# 3.net
KiCad netlist of a schematic drawn in EasyEDA Pro
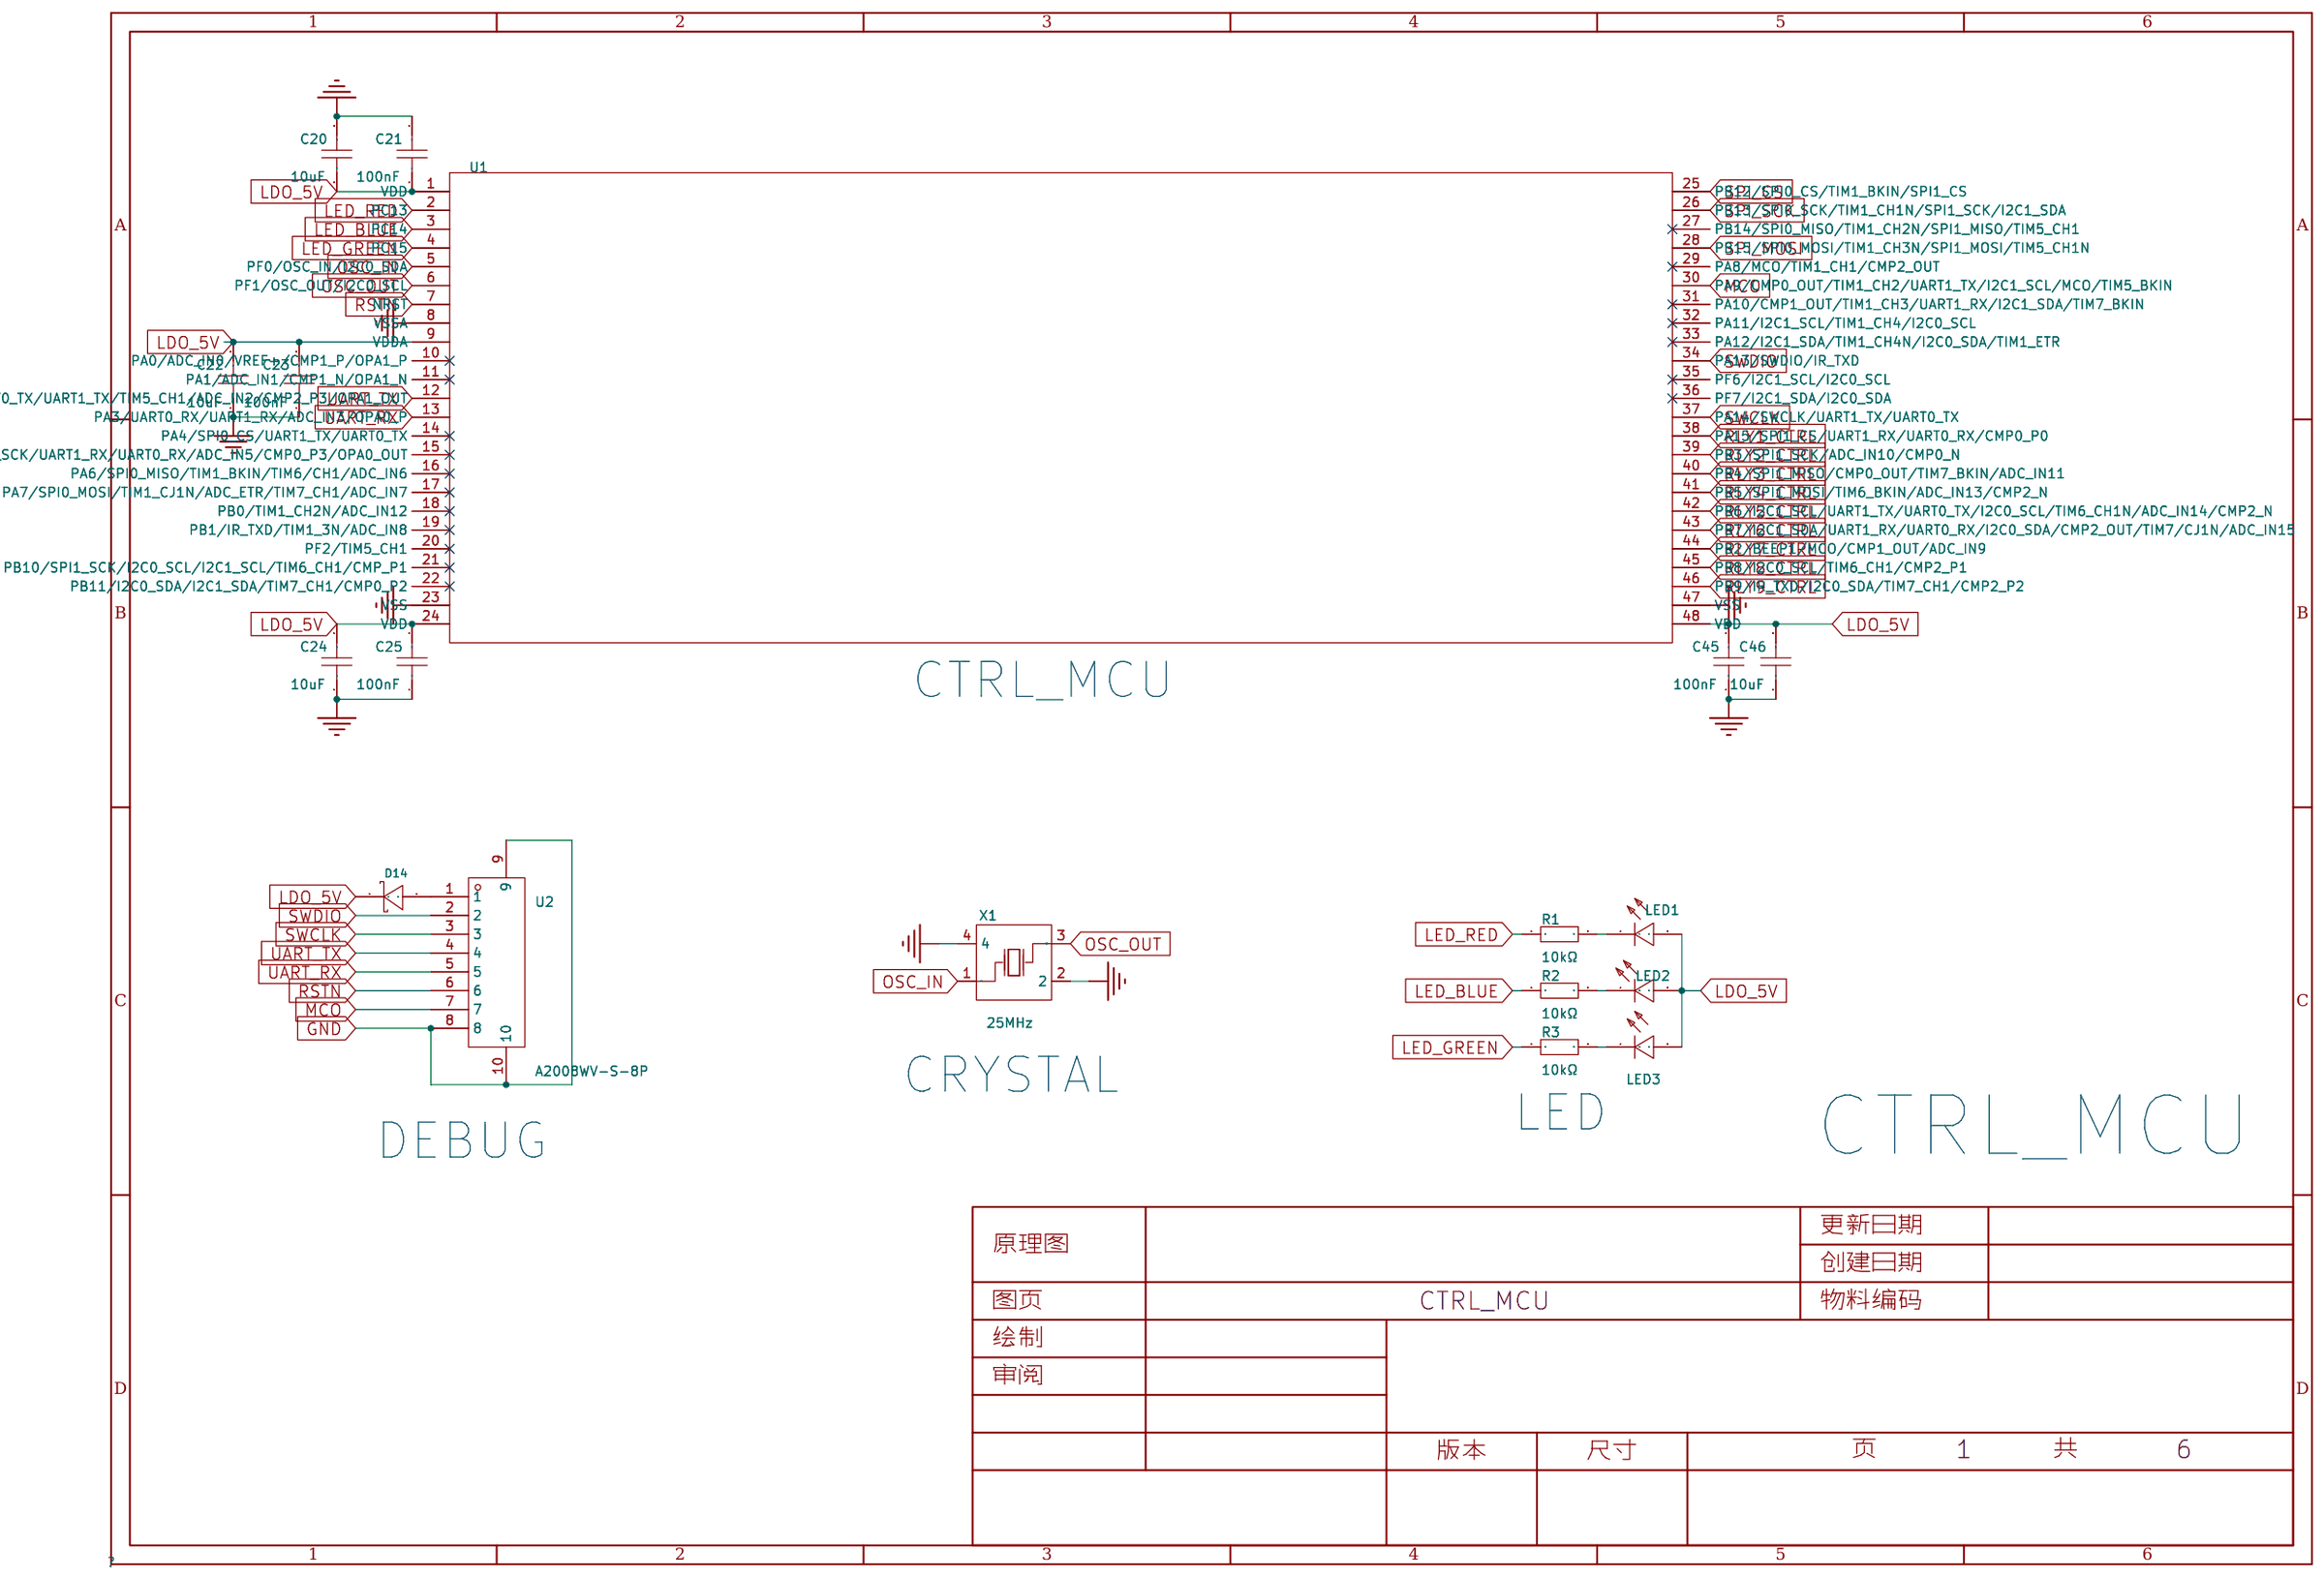
[diagram p0: CTRL_MCU]
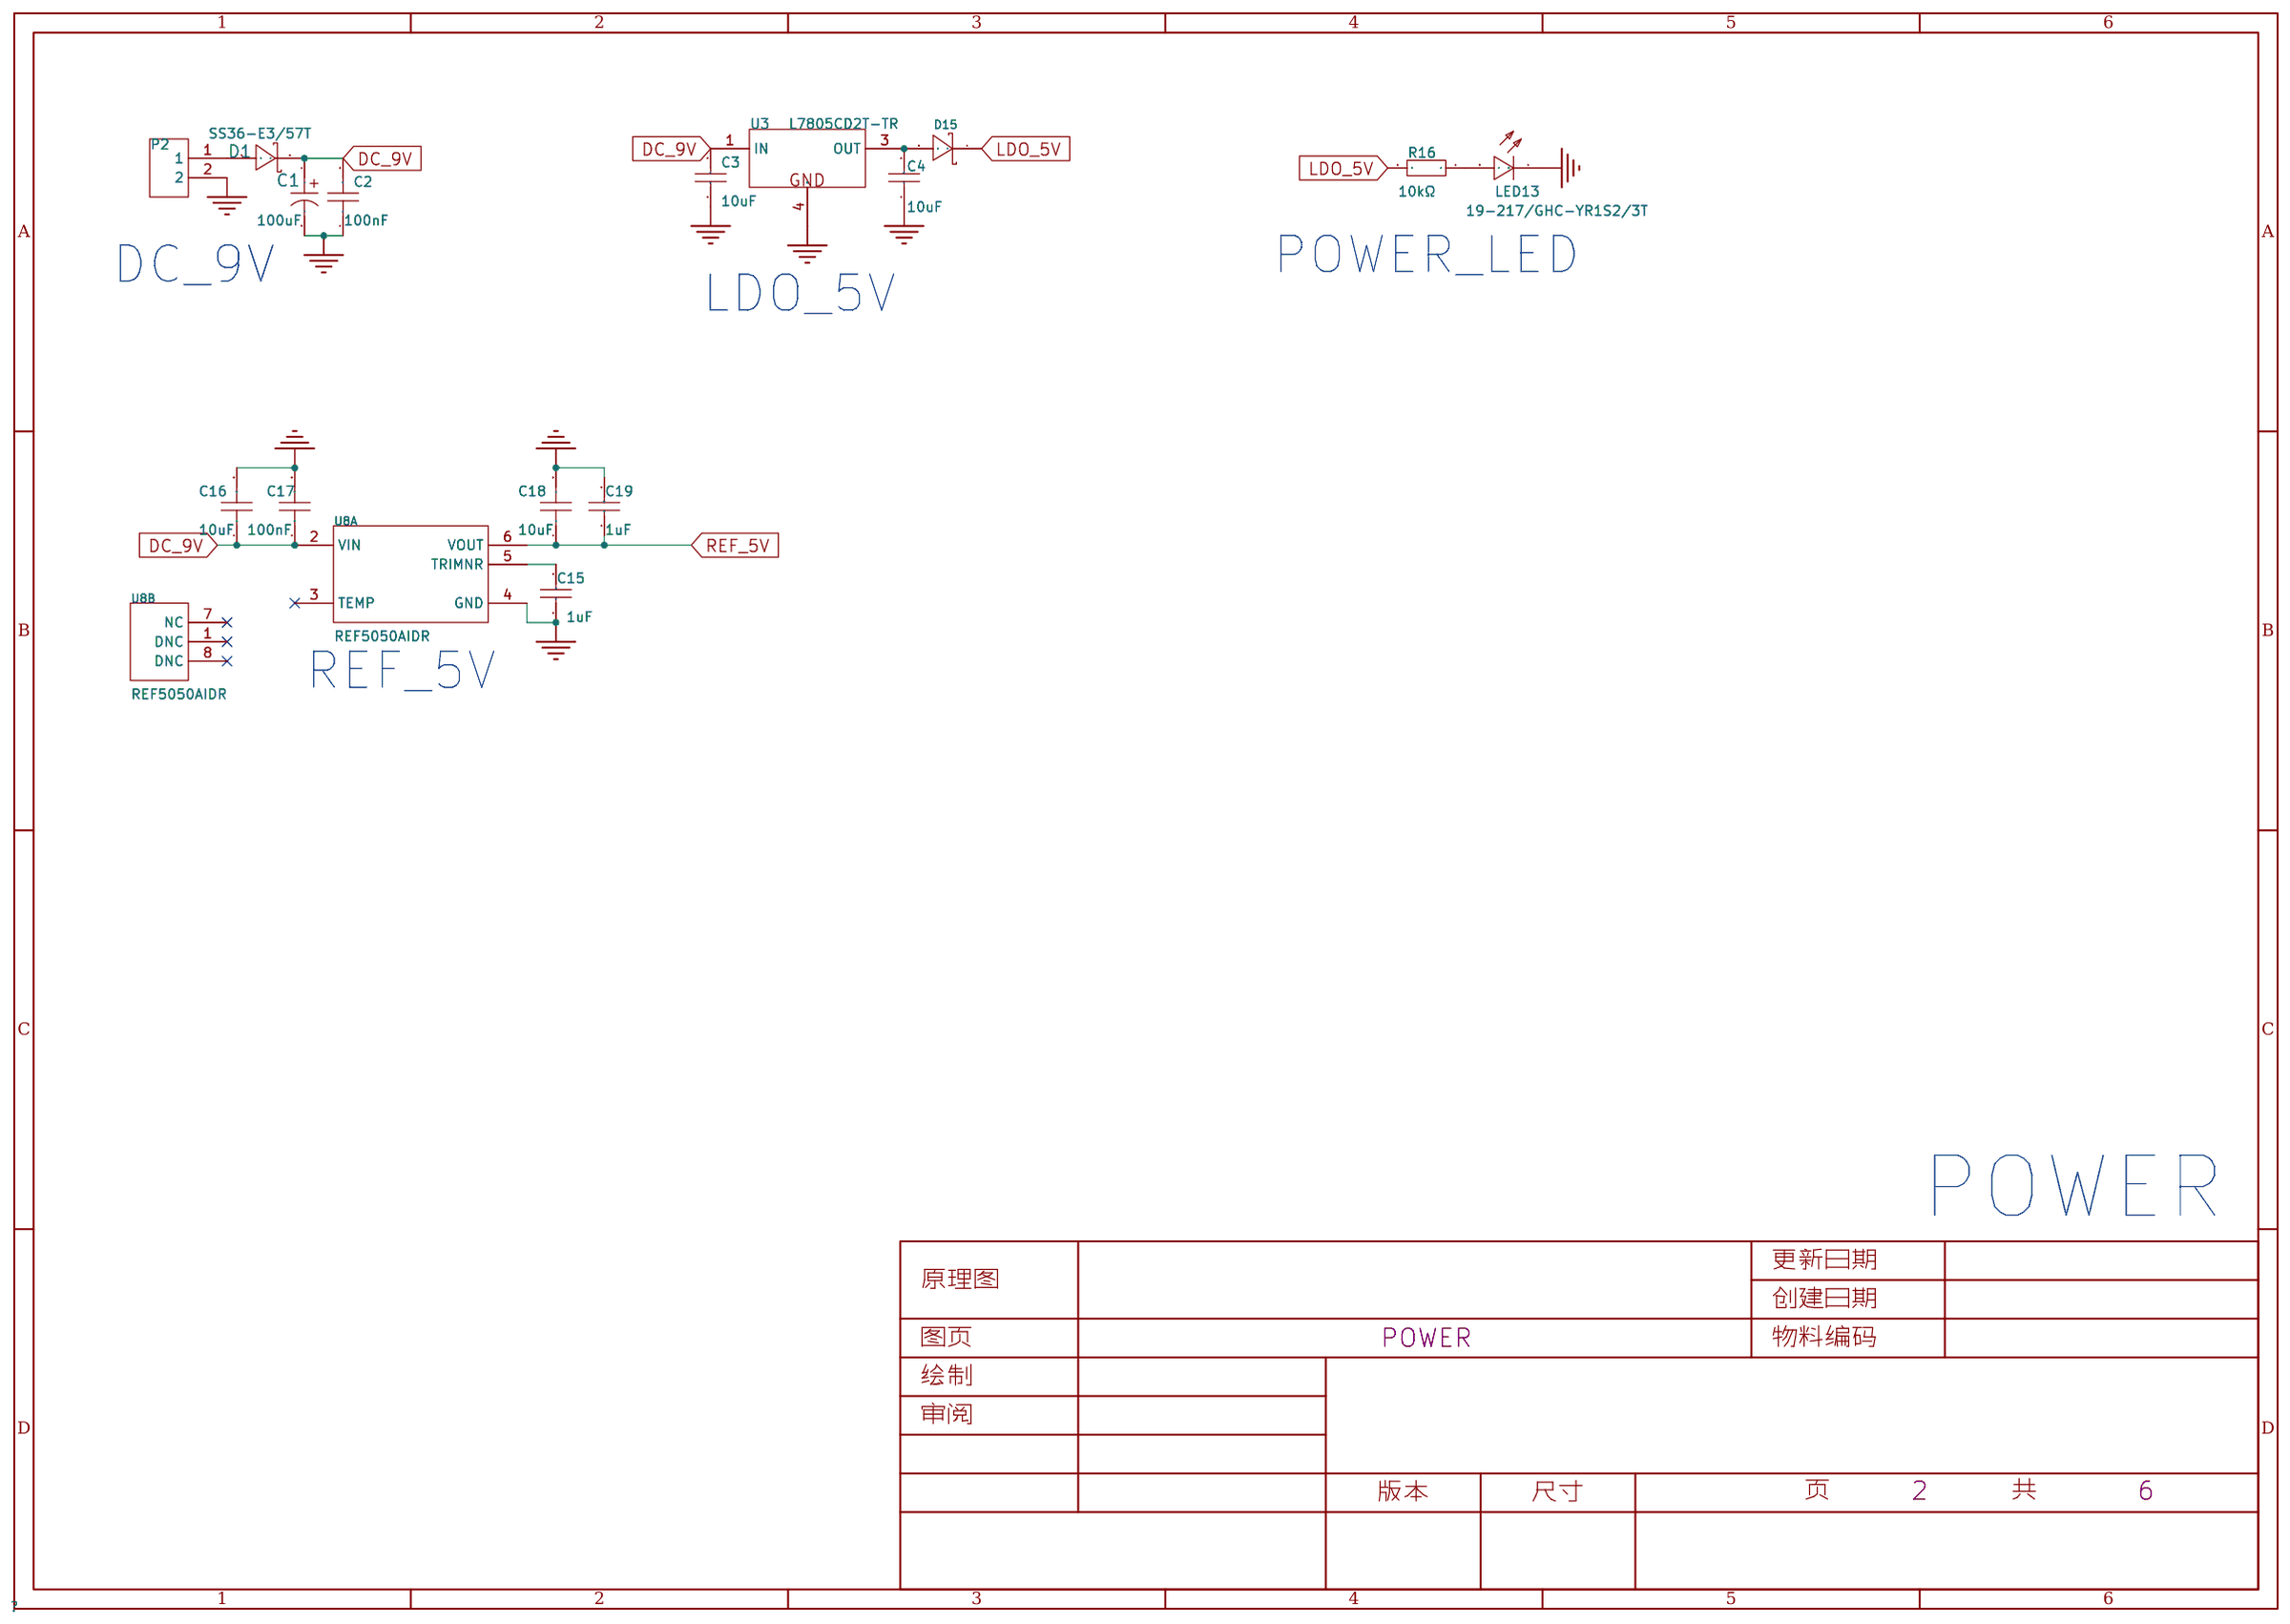
[diagram p1: POWER]
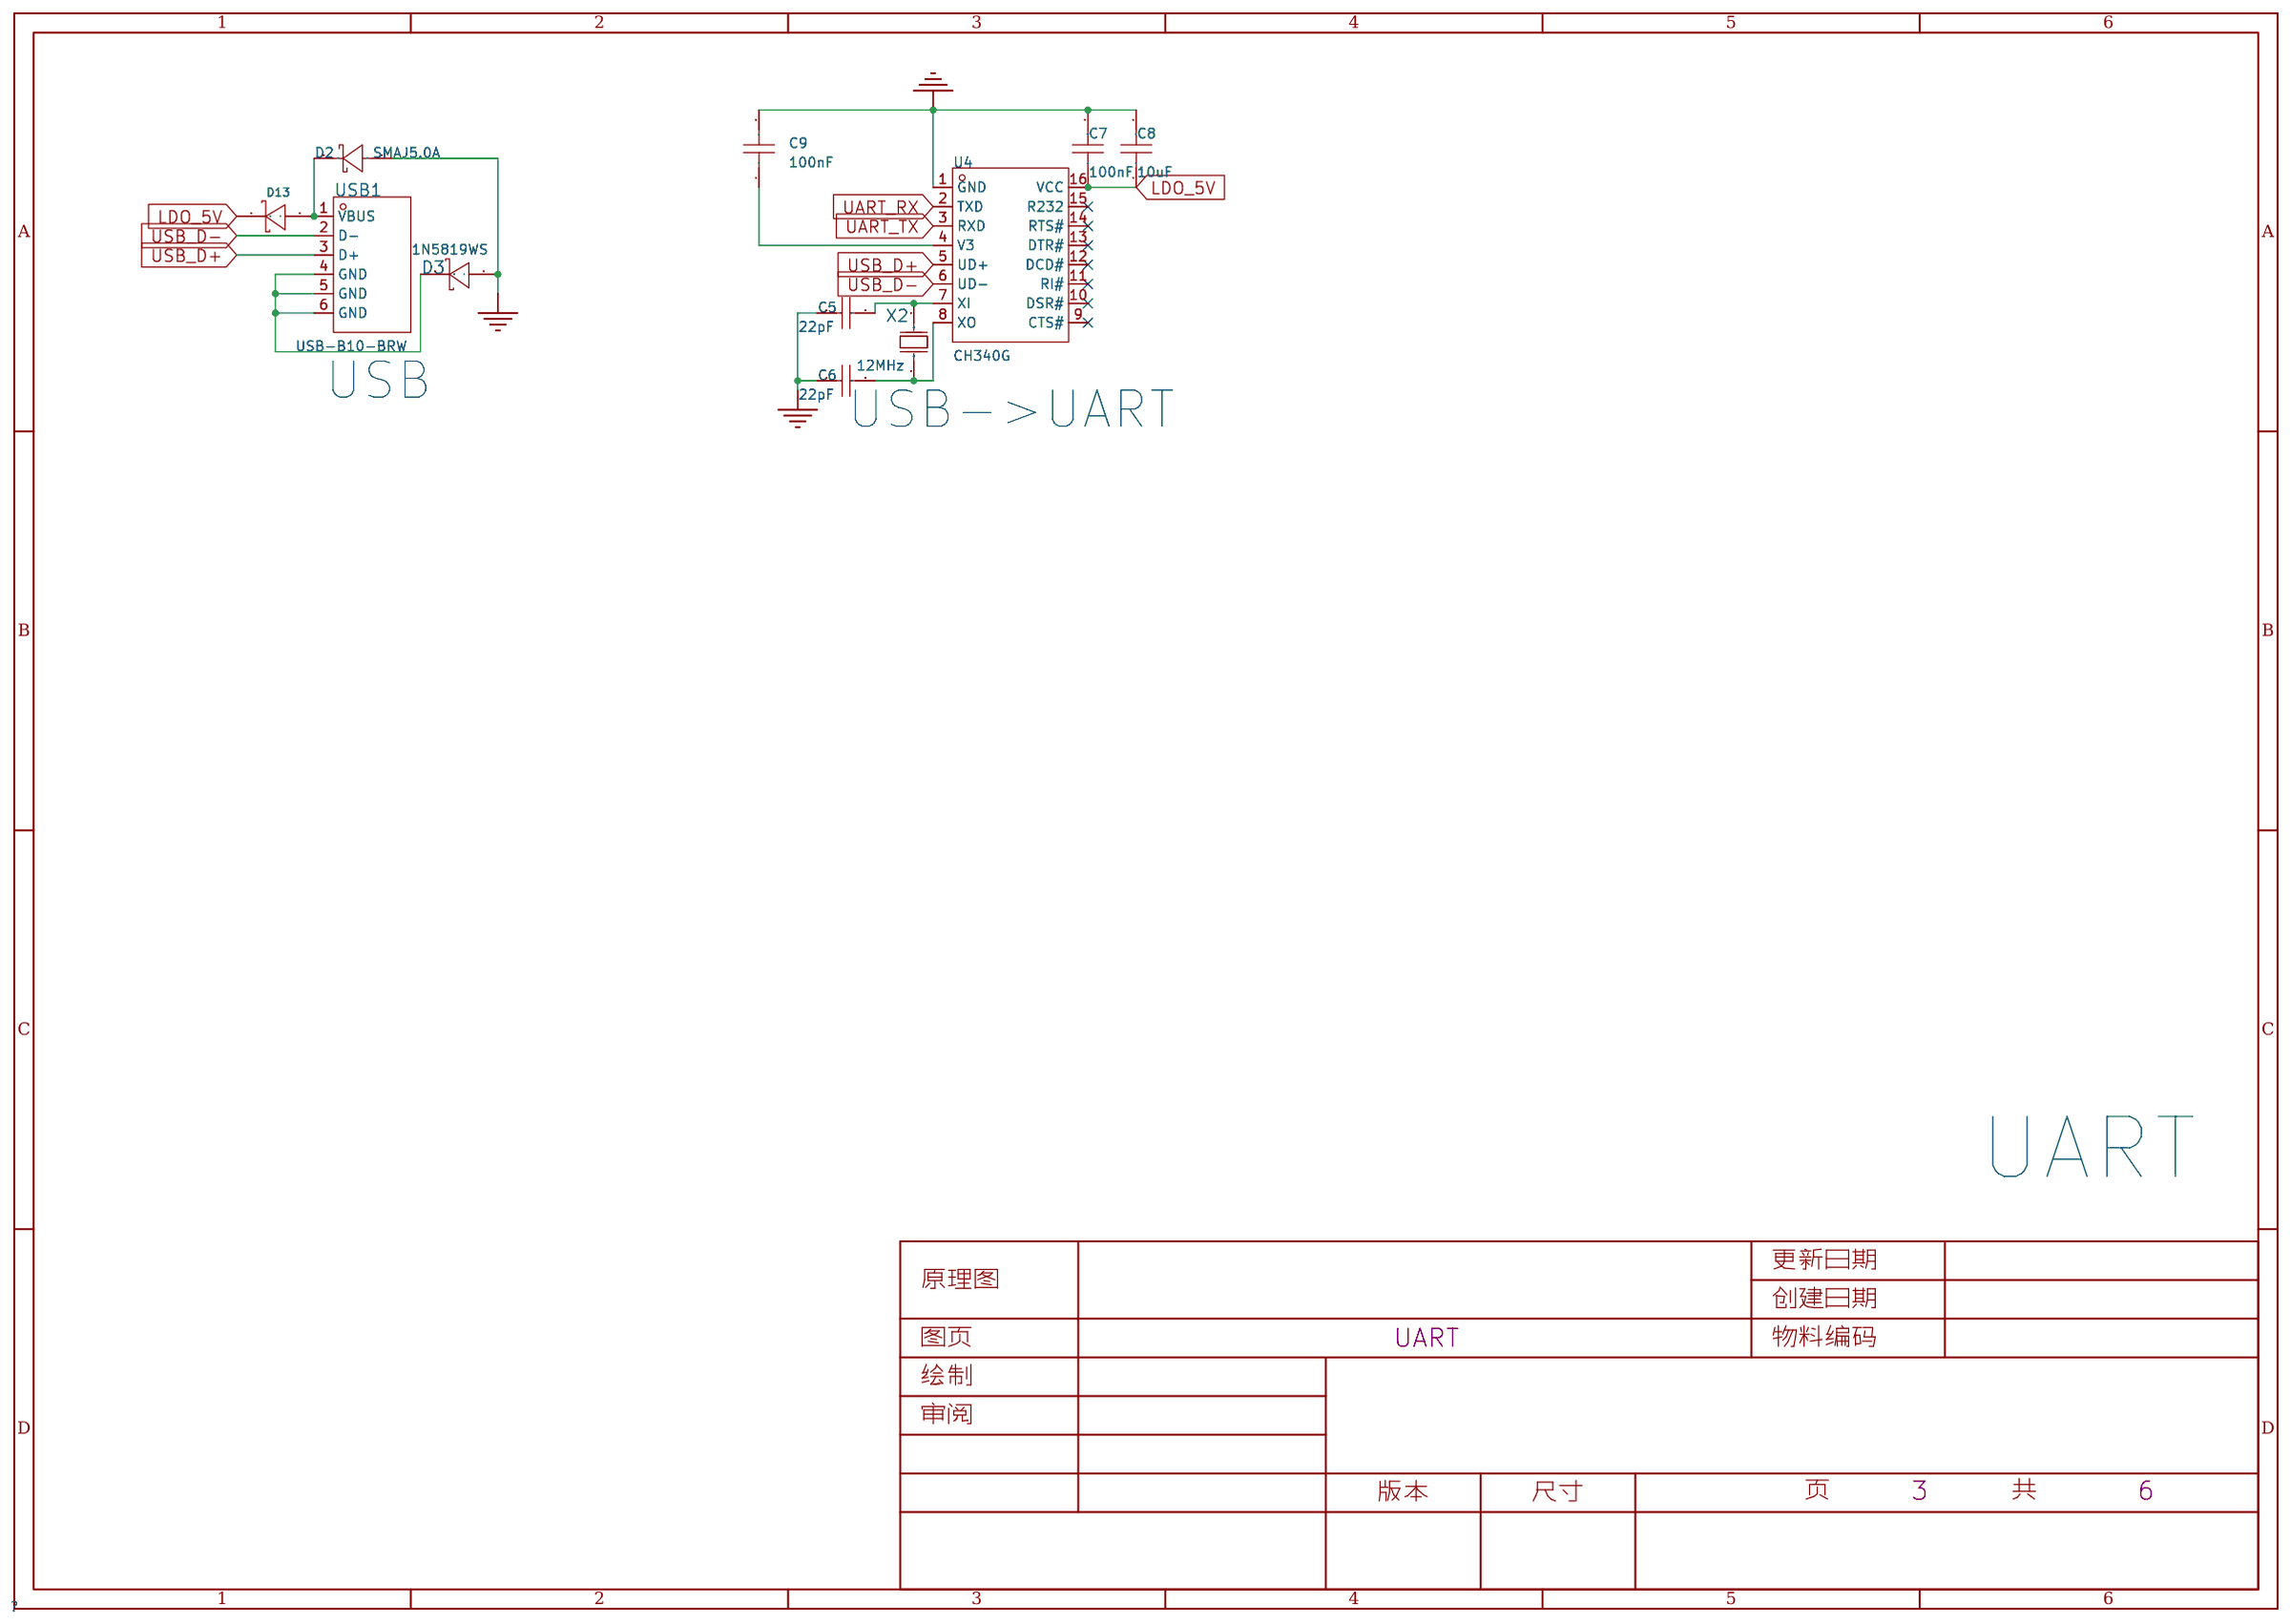
[diagram p2: UART]
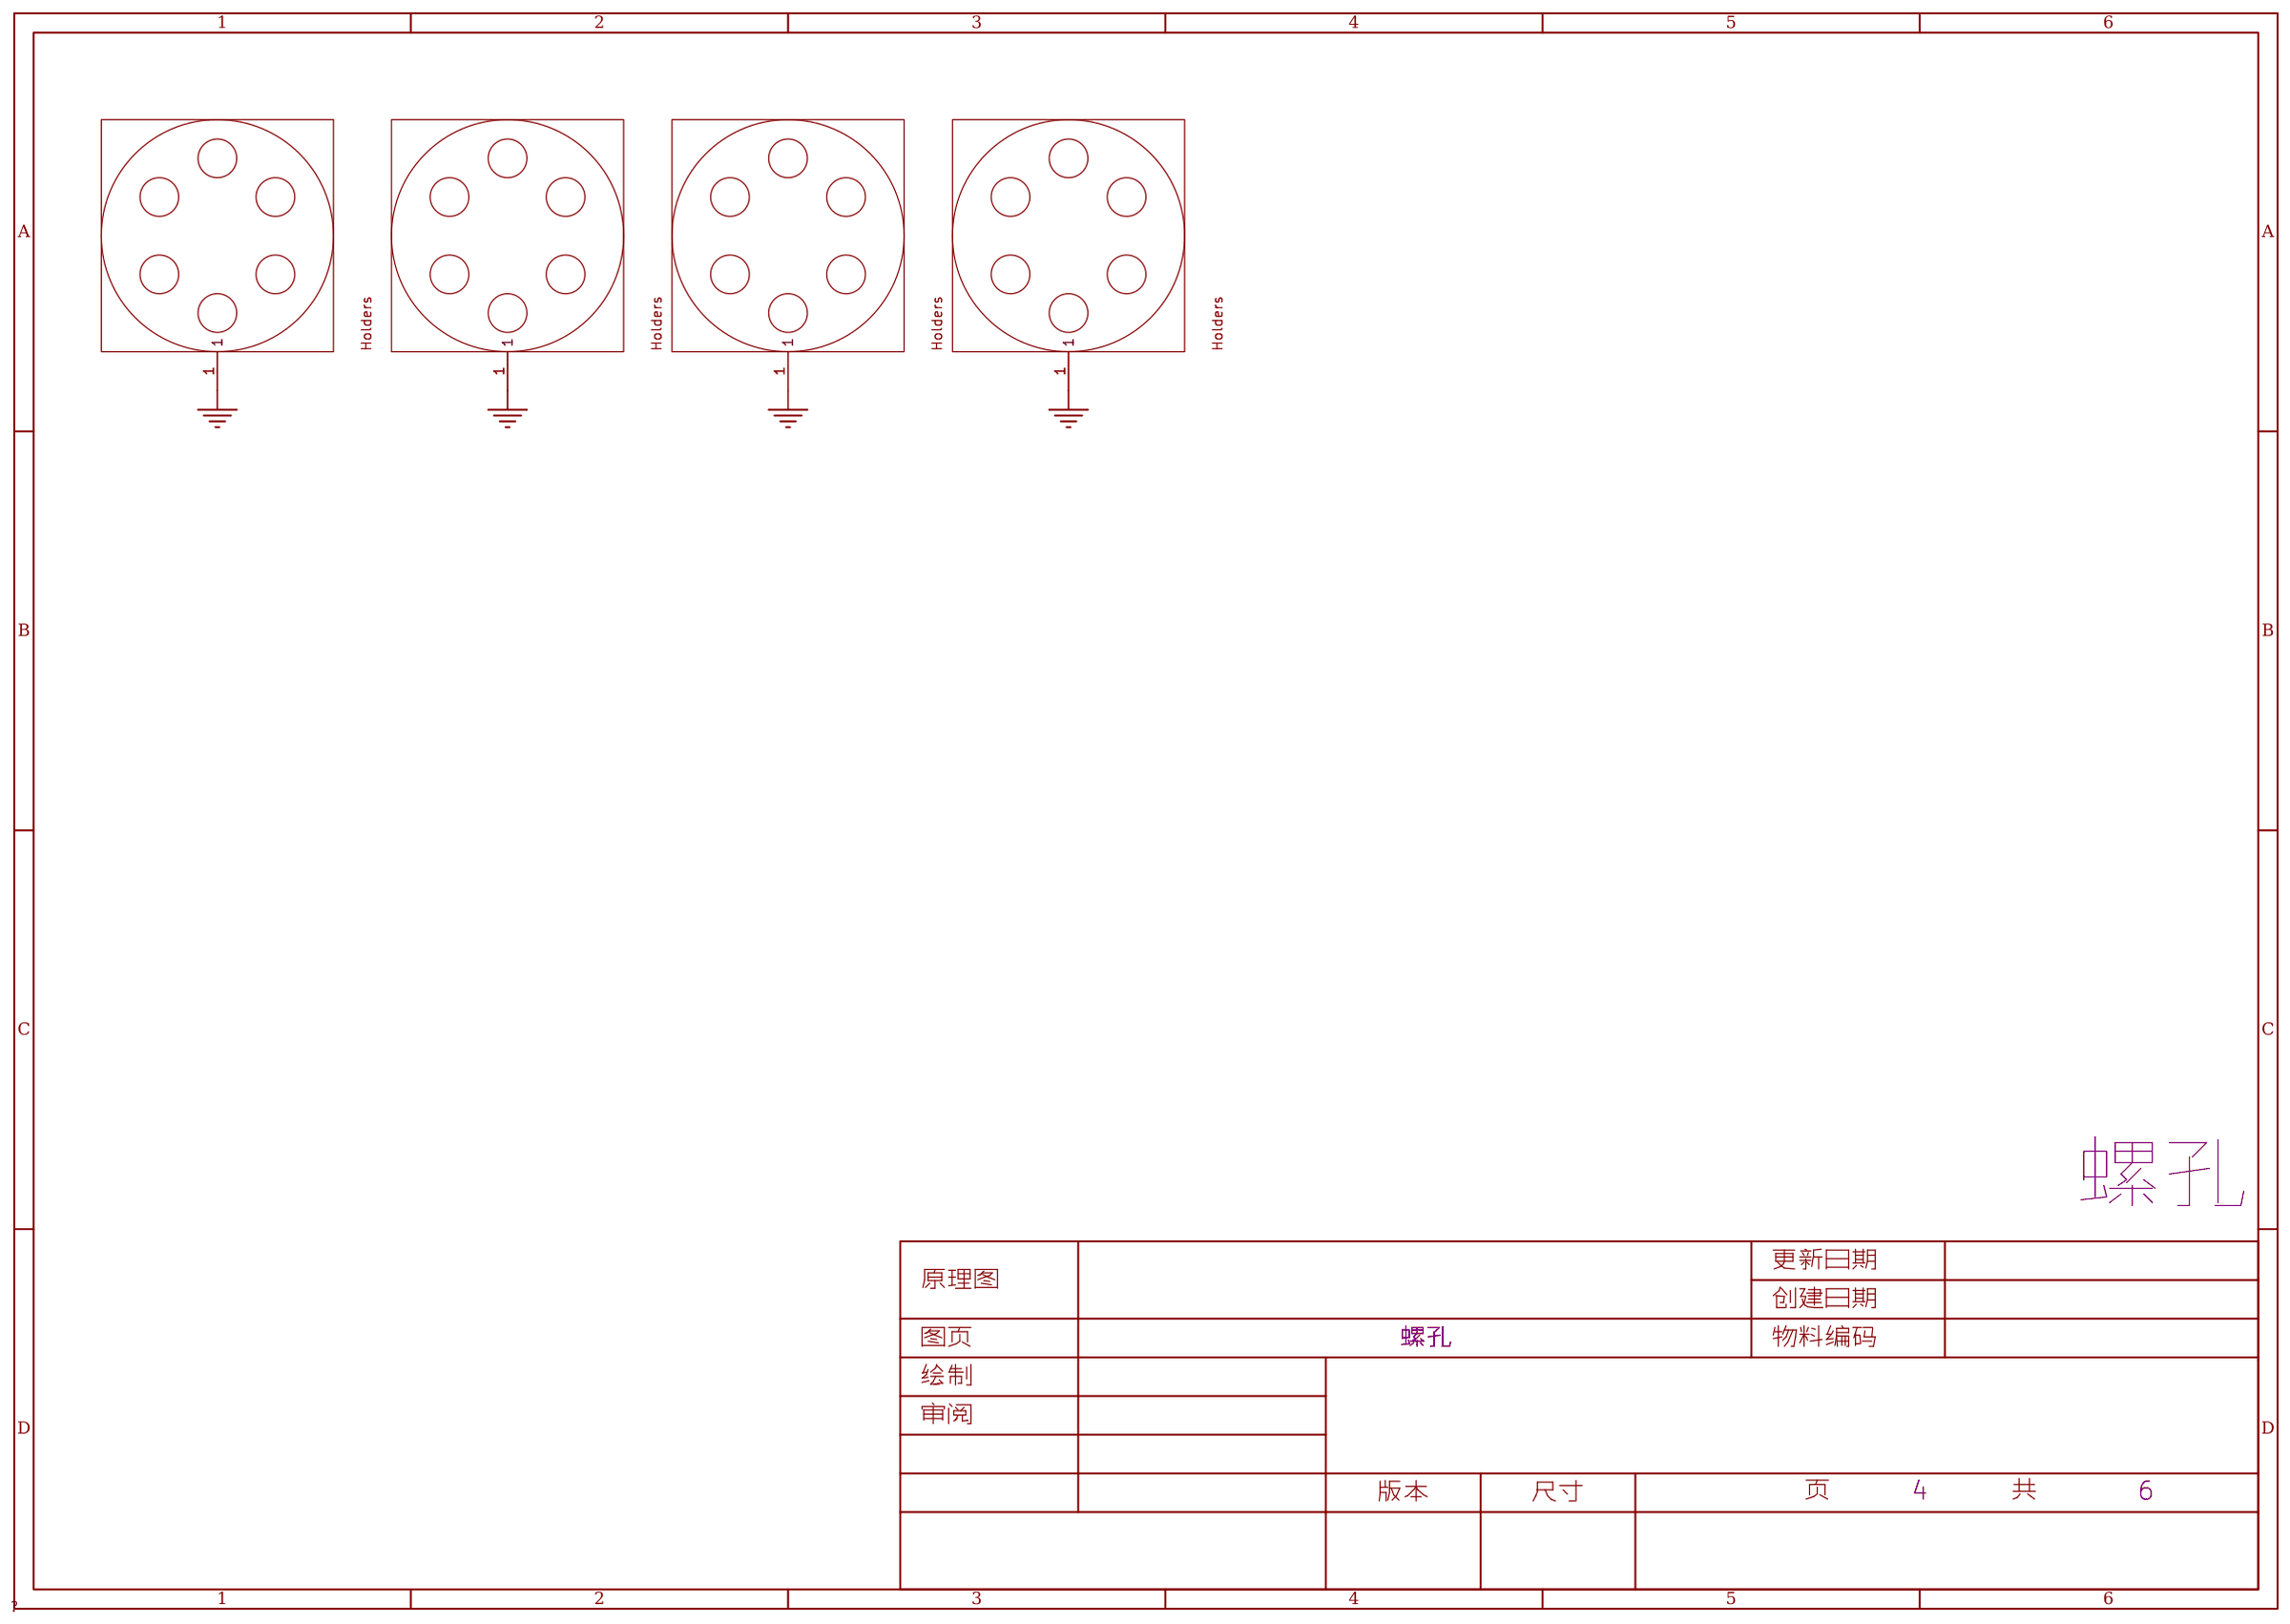
[diagram p3: 螺孔]
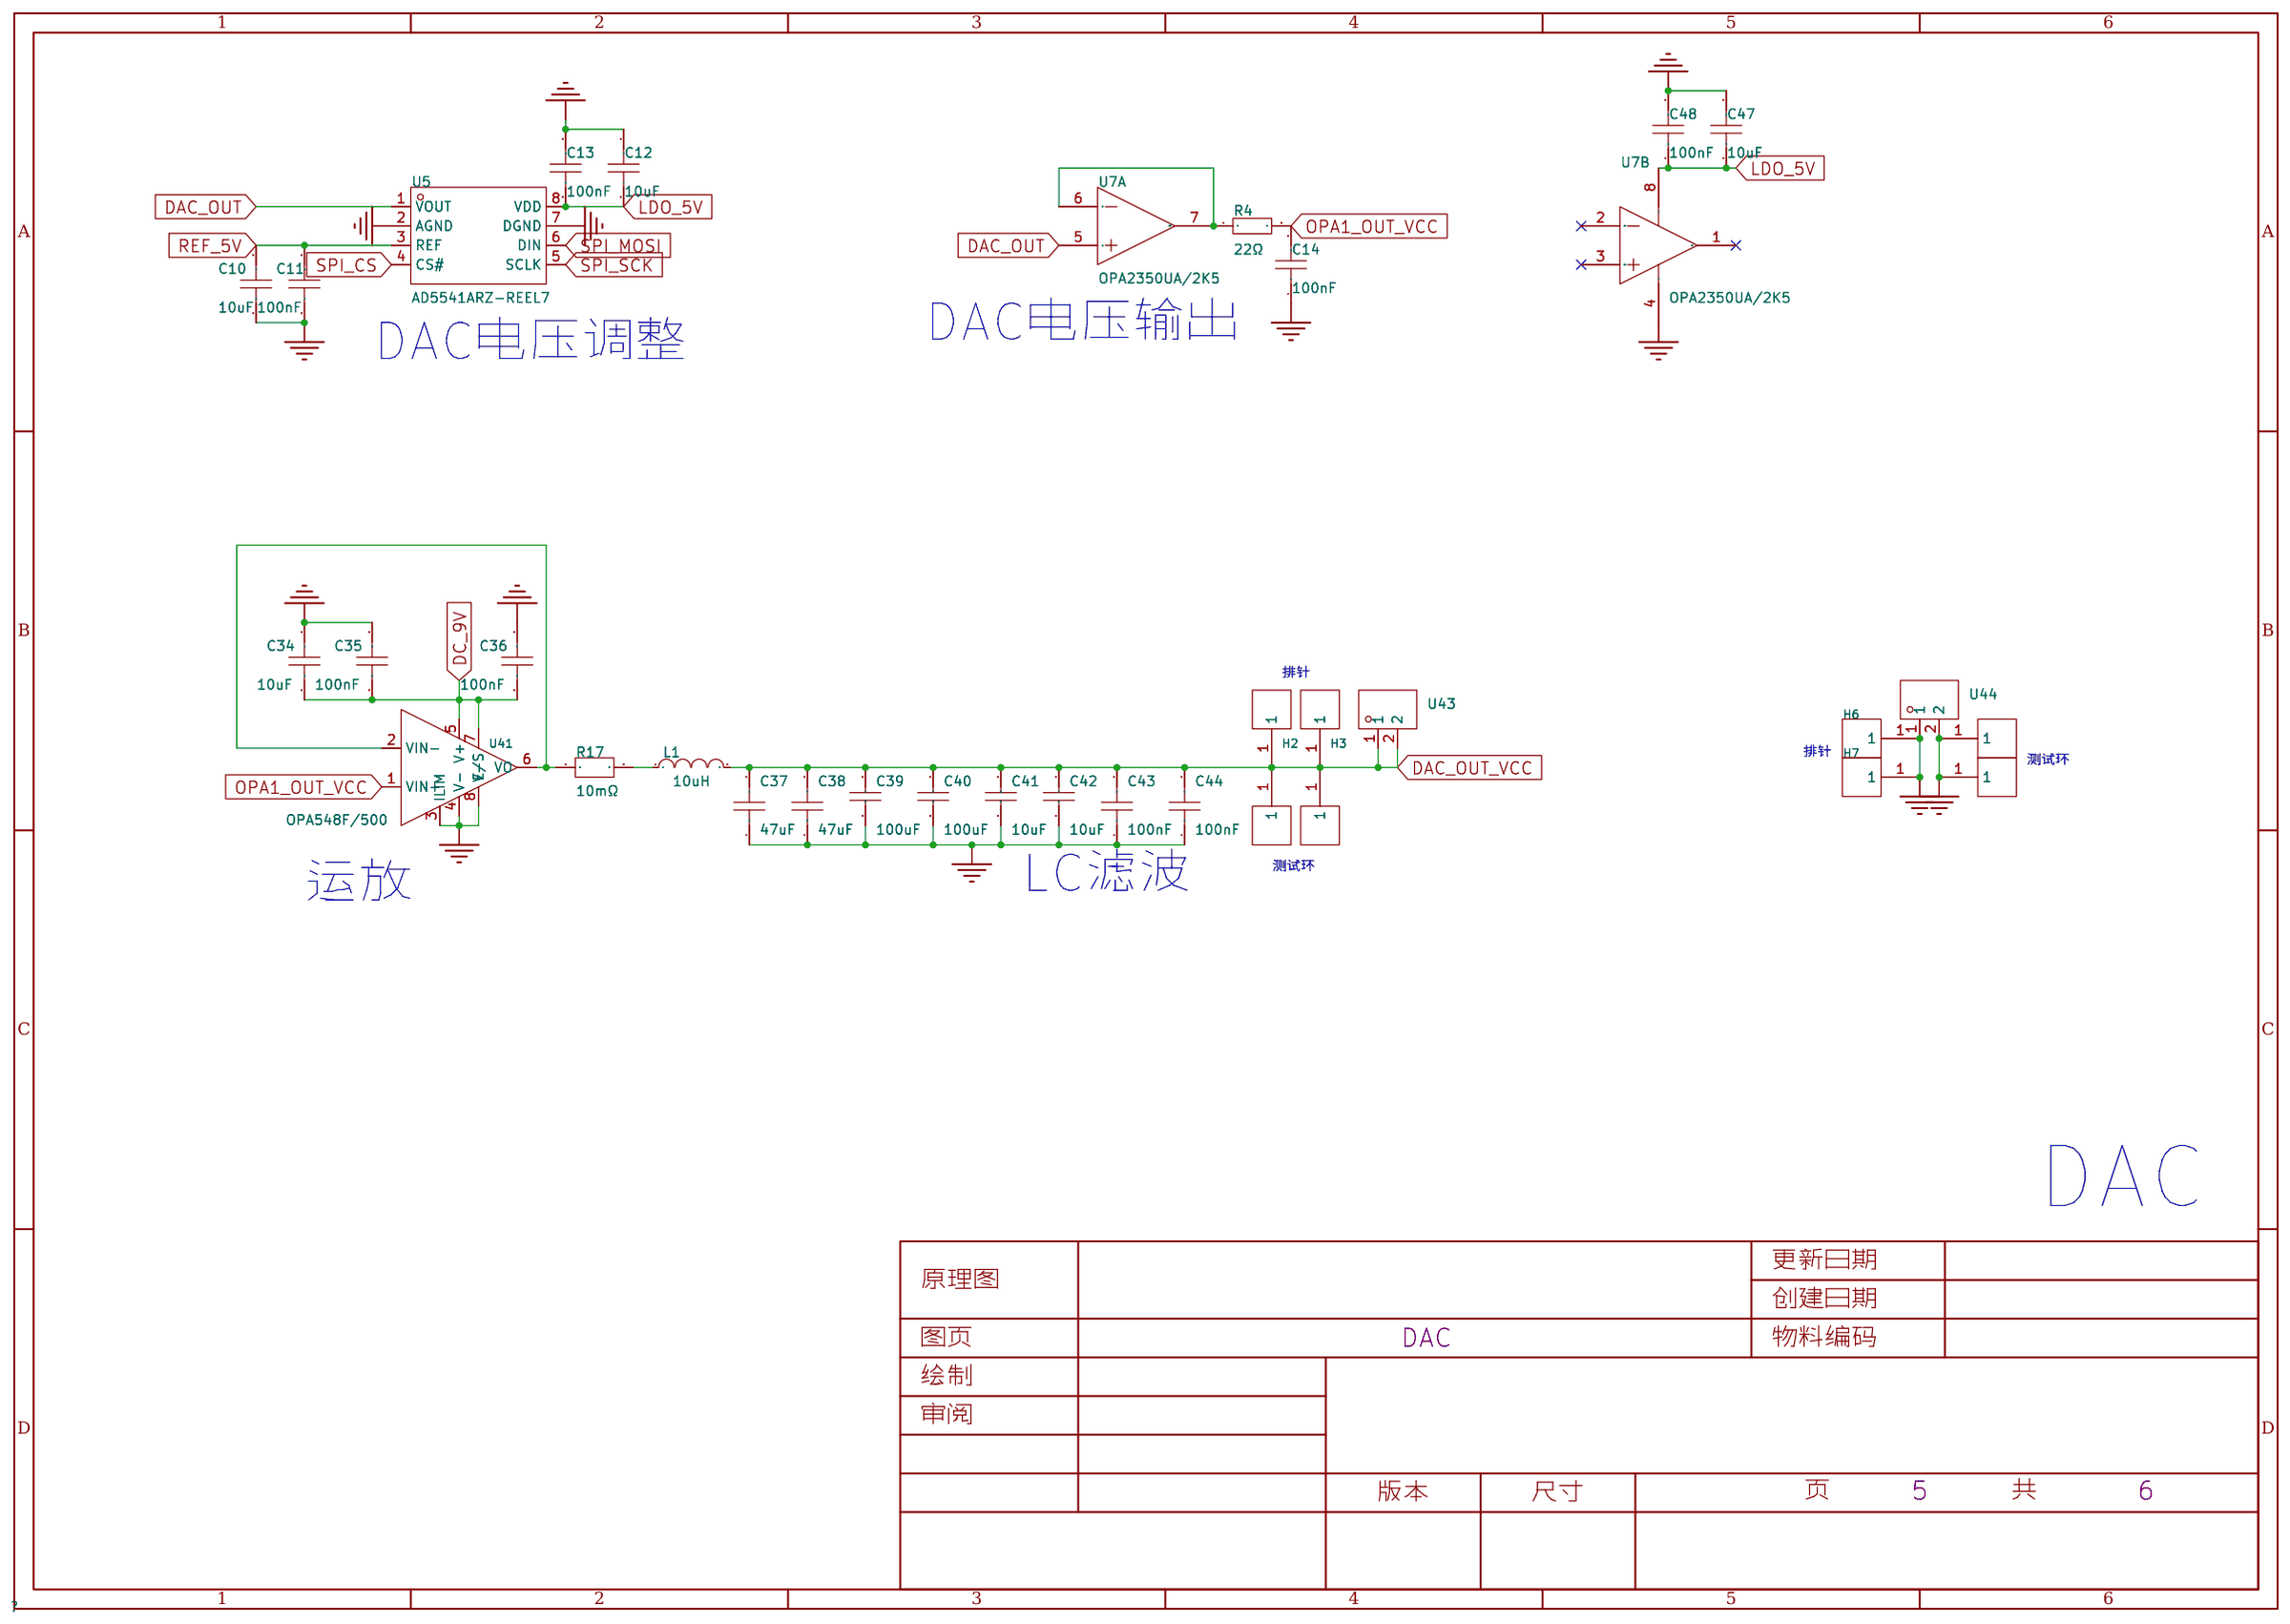
[diagram p4: DAC]
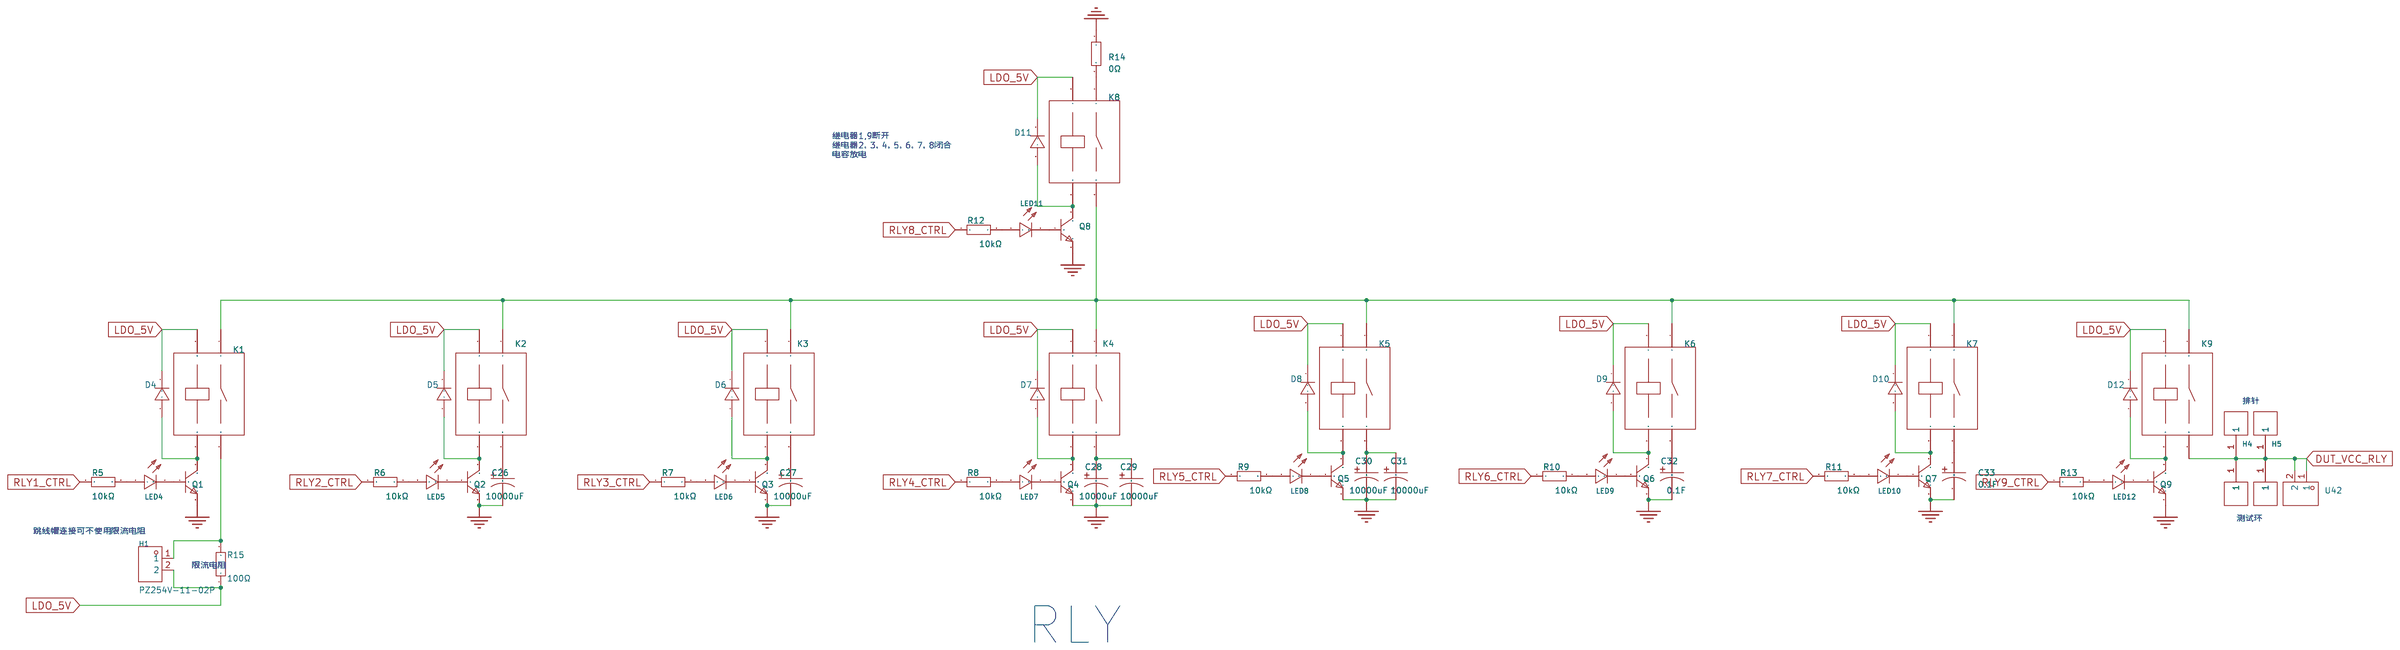
[diagram p5: RLY]

(export (version "E")
  (design (tool "Eeschema 10.0.6"))
  (components
    (comp (ref "C20")
      (value "10uF")
      (footprint "easyedapro:C0603")
      (description "容值:10uF;精度:±20%;额定电压:25V;材质(温度系数):X5R;")
      (fields
        (field (name "Manufacturer Part") "CL10A106MA8NRNC")
        (field (name "Manufacturer") "SAMSUNG(三星)")
      )
      (libsource (lib "easyedapro") (part "CL10A106MA8NRNC"))
    )
    (comp (ref "C21")
      (value "100nF")
      (footprint "easyedapro:C0603")
      (description "容值:100nF;精度:±10%;额定电压:50V;材质(温度系数):X7R;")
      (fields
        (field (name "Manufacturer Part") "CC0603KRX7R9BB104")
        (field (name "Manufacturer") "YAGEO(国巨)")
      )
      (libsource (lib "easyedapro") (part "CC0603KRX7R9BB104"))
    )
    (comp (ref "C22")
      (value "10uF")
      (footprint "easyedapro:C0603")
      (description "容值:10uF;精度:±20%;额定电压:25V;材质(温度系数):X5R;")
      (fields
        (field (name "Manufacturer Part") "CL10A106MA8NRNC")
        (field (name "Manufacturer") "SAMSUNG(三星)")
      )
      (libsource (lib "easyedapro") (part "CL10A106MA8NRNC"))
    )
    (comp (ref "C23")
      (value "100nF")
      (footprint "easyedapro:C0603")
      (description "容值:100nF;精度:±10%;额定电压:50V;材质(温度系数):X7R;")
      (fields
        (field (name "Manufacturer Part") "CC0603KRX7R9BB104")
        (field (name "Manufacturer") "YAGEO(国巨)")
      )
      (libsource (lib "easyedapro") (part "CC0603KRX7R9BB104"))
    )
    (comp (ref "C24")
      (value "10uF")
      (footprint "easyedapro:C0603")
      (description "容值:10uF;精度:±20%;额定电压:25V;材质(温度系数):X5R;")
      (fields
        (field (name "Manufacturer Part") "CL10A106MA8NRNC")
        (field (name "Manufacturer") "SAMSUNG(三星)")
      )
      (libsource (lib "easyedapro") (part "CL10A106MA8NRNC"))
    )
    (comp (ref "C25")
      (value "100nF")
      (footprint "easyedapro:C0603")
      (description "容值:100nF;精度:±10%;额定电压:50V;材质(温度系数):X7R;")
      (fields
        (field (name "Manufacturer Part") "CC0603KRX7R9BB104")
        (field (name "Manufacturer") "YAGEO(国巨)")
      )
      (libsource (lib "easyedapro") (part "CC0603KRX7R9BB104"))
    )
    (comp (ref "C45")
      (value "100nF")
      (footprint "easyedapro:C0603")
      (description "容值:100nF;精度:±10%;额定电压:50V;材质(温度系数):X7R;")
      (fields
        (field (name "Manufacturer Part") "CC0603KRX7R9BB104")
        (field (name "Manufacturer") "YAGEO(国巨)")
      )
      (libsource (lib "easyedapro") (part "CC0603KRX7R9BB104"))
    )
    (comp (ref "C46")
      (value "10uF")
      (footprint "easyedapro:C0603")
      (description "容值:10uF;精度:±20%;额定电压:25V;材质(温度系数):X5R;")
      (fields
        (field (name "Manufacturer Part") "CL10A106MA8NRNC")
        (field (name "Manufacturer") "SAMSUNG(三星)")
      )
      (libsource (lib "easyedapro") (part "CL10A106MA8NRNC"))
    )
    (comp (ref "D14")
      (value "1N5819WS")
      (footprint "easyedapro:SOD-323_L1.8-W1.3-LS2.5-RD")
      (description "直流反向耐压(Vr):40V;平均整流电流(Io):1A;正向压降(Vf):600mV@1A;")
      (fields (field (name "Manufacturer") "Hottech(合科泰)"))
      (libsource (lib "easyedapro") (part "1N5819WS"))
    )
    (comp (ref "LED1")
      (value "NCD0603R1")
      (footprint "easyedapro:LED0603-RD_RED")
      (description "发光颜色:红灯;")
      (fields (field (name "Manufacturer") "国星光电"))
      (libsource (lib "easyedapro") (part "FC-DA1608HRK-620D"))
    )
    (comp (ref "LED2")
      (value "19-217/BHC-ZL1M2RY/3T")
      (footprint "easyedapro:LED0603-FD_BLUE")
      (description "发光颜色:蓝灯;二极管配置:-;主波长:465nm~475nm;色温:-;功率:110mW;安装方式:-;")
      (fields (field (name "Manufacturer") "EVERLIGHT(亿光)"))
      (libsource (lib "easyedapro") (part "19-217/BHC-ZL1M2RY/3T"))
    )
    (comp (ref "LED3")
      (value "19-217/GHC-YR1S2/3T")
      (footprint "easyedapro:LED0603-RD")
      (description "发光颜色:翠绿;二极管配置:-;主波长:520nm~535nm;色温:-;功率:110mW;安装方式:-;")
      (fields (field (name "Manufacturer") "EVERLIGHT(亿光)"))
      (libsource (lib "easyedapro") (part "19-217/GHC-YR1S2/3T"))
    )
    (comp (ref "R1")
      (value "10kΩ")
      (footprint "easyedapro:R0603")
      (description "电阻类型:厚膜电阻;阻值:10kΩ;精度:±1%;功率:100mW;")
      (fields
        (field (name "Manufacturer Part") "0603WAF1002T5E")
        (field (name "Manufacturer") "UNI-ROYAL(厚声)")
      )
      (libsource (lib "easyedapro") (part "0603WAF1002T5E"))
    )
    (comp (ref "R2")
      (value "10kΩ")
      (footprint "easyedapro:R0603")
      (description "电阻类型:厚膜电阻;阻值:10kΩ;精度:±1%;功率:100mW;")
      (fields
        (field (name "Manufacturer Part") "0603WAF1002T5E")
        (field (name "Manufacturer") "UNI-ROYAL(厚声)")
      )
      (libsource (lib "easyedapro") (part "0603WAF1002T5E"))
    )
    (comp (ref "R3")
      (value "10kΩ")
      (footprint "easyedapro:R0603")
      (description "电阻类型:厚膜电阻;阻值:10kΩ;精度:±1%;功率:100mW;")
      (fields
        (field (name "Manufacturer Part") "0603WAF1002T5E")
        (field (name "Manufacturer") "UNI-ROYAL(厚声)")
      )
      (libsource (lib "easyedapro") (part "0603WAF1002T5E"))
    )
    (comp (ref "U1") (value "PT32A030C8T7") (libsource (lib "easyedapro") (part "PT32A030C8T7")))
    (comp (ref "U2")
      (value "A2008WV-S-8P")
      (footprint "easyedapro:CONN-SMD_A2008WV-S-8P")
      (description "参考系列:PH;间距:2mm;插针结构:1x8P;排数:1;每排PIN数:8;行距:-;安装方式:-;触头材质:黄铜;")
      (fields (field (name "Manufacturer") "CJT(长江连接器)"))
      (libsource (lib "easyedapro") (part "A2008WV-S-8P"))
    )
    (comp (ref "X1")
      (value "25MHz")
      (footprint "easyedapro:OSC-SMD_4P-L2.5-W2.0-BL")
      (description "晶振类型:-;频率:25MHz;频率公差:±25ppm;频率稳定度:±50ppm;负载电容:10pF;等效串联电阻(ESR):60Ω;工作温度:-40°C~+125°C;")
      (fields (field (name "Manufacturer Part") "ECS-250-10-36Q-AES-TR") (field (name "Manufacturer") "ECS"))
      (libsource (lib "easyedapro") (part "ECS-250-10-36Q-AES-TR"))
    )
    (comp (ref "C1")
      (value "100uF")
      (footprint "easyedapro:CAP-SMD_BD6.3-L6.6-W6.6-LS7.6-FD-1")
      (description "容值:100uF;精度:±20%;额定电压:35V;纹波电流:230mA@120Hz;等效串联电阻:600mΩ@100kHz;")
      (fields
        (field (name "Manufacturer Part") "RVE100UF35V67RV0072")
        (field (name "Manufacturer") "KNSCHA(科尼盛)")
      )
      (libsource (lib "easyedapro") (part "RVE100UF35V67RV0072"))
    )
    (comp (ref "C2")
      (value "100nF")
      (footprint "easyedapro:C0603")
      (description "容值:100nF;精度:±10%;额定电压:50V;材质(温度系数):X7R;")
      (fields
        (field (name "Manufacturer Part") "CL10B104KB8NNNC")
        (field (name "Manufacturer") "SAMSUNG(三星)")
      )
      (libsource (lib "easyedapro") (part "CL10B104KB8NNNC"))
    )
    (comp (ref "C3")
      (value "10uF")
      (footprint "easyedapro:C1206")
      (description "容值:10uF;精度:±10%;额定电压:50V;材质(温度系数):X5R;")
      (fields
        (field (name "Manufacturer Part") "CL31A106KBHNNNE")
        (field (name "Manufacturer") "SAMSUNG(三星)")
      )
      (libsource (lib "easyedapro") (part "CL31A106KBHNNNE"))
    )
    (comp (ref "C4")
      (value "10uF")
      (footprint "easyedapro:C1206")
      (description "容值:10uF;精度:±10%;额定电压:50V;材质(温度系数):X5R;")
      (fields
        (field (name "Manufacturer Part") "CL31A106KBHNNNE")
        (field (name "Manufacturer") "SAMSUNG(三星)")
      )
      (libsource (lib "easyedapro") (part "CL31A106KBHNNNE"))
    )
    (comp (ref "C15")
      (value "1uF")
      (footprint "easyedapro:C0603")
      (description "容值:1uF;精度:±10%;额定电压:50V;材质(温度系数):X5R;")
      (fields
        (field (name "Manufacturer Part") "CL10A105KB8NNNC")
        (field (name "Manufacturer") "SAMSUNG(三星)")
      )
      (libsource (lib "easyedapro") (part "CL10A105KB8NNNC"))
    )
    (comp (ref "C16")
      (value "10uF")
      (footprint "easyedapro:C0603")
      (description "容值:10uF;精度:±20%;额定电压:25V;材质(温度系数):X5R;")
      (fields
        (field (name "Manufacturer Part") "CL10A106MA8NRNC")
        (field (name "Manufacturer") "SAMSUNG(三星)")
      )
      (libsource (lib "easyedapro") (part "CL10A106MA8NRNC"))
    )
    (comp (ref "C17")
      (value "100nF")
      (footprint "easyedapro:C0603")
      (description "容值:100nF;精度:±10%;额定电压:50V;材质(温度系数):X7R;")
      (fields
        (field (name "Manufacturer Part") "CC0603KRX7R9BB104")
        (field (name "Manufacturer") "YAGEO(国巨)")
      )
      (libsource (lib "easyedapro") (part "CC0603KRX7R9BB104"))
    )
    (comp (ref "C18")
      (value "10uF")
      (footprint "easyedapro:C0603")
      (description "容值:10uF;精度:±20%;额定电压:25V;材质(温度系数):X5R;")
      (fields
        (field (name "Manufacturer Part") "CL10A106MA8NRNC")
        (field (name "Manufacturer") "SAMSUNG(三星)")
      )
      (libsource (lib "easyedapro") (part "CL10A106MA8NRNC"))
    )
    (comp (ref "C19")
      (value "1uF")
      (footprint "easyedapro:C0603")
      (description "容值:1uF;精度:±10%;额定电压:50V;材质(温度系数):X5R;")
      (fields
        (field (name "Manufacturer Part") "CL10A105KB8NNNC")
        (field (name "Manufacturer") "SAMSUNG(三星)")
      )
      (libsource (lib "easyedapro") (part "CL10A105KB8NNNC"))
    )
    (comp (ref "D1")
      (value "SS36-E3/57T")
      (footprint "easyedapro:SMC_L7.1-W6.2-LS8.1-R-RD")
      (description "直流反向耐压（Vr）:60V;平均整流电流（Io）:3A;正向压降（Vf）:750mV @ 3A;")
      (fields (field (name "Manufacturer") "VISHAY(威世)"))
      (libsource (lib "easyedapro") (part "SS36-E3/57T"))
    )
    (comp (ref "D15")
      (value "1N5819WS")
      (footprint "easyedapro:SOD-323_L1.8-W1.3-LS2.5-RD")
      (description "直流反向耐压(Vr):40V;平均整流电流(Io):1A;正向压降(Vf):600mV@1A;")
      (fields (field (name "Manufacturer") "Hottech(合科泰)"))
      (libsource (lib "easyedapro") (part "1N5819WS"))
    )
    (comp (ref "LED13")
      (value "19-217/GHC-YR1S2/3T")
      (footprint "easyedapro:LED0603-RD")
      (description "发光颜色:翠绿;二极管配置:-;主波长:520nm~535nm;色温:-;功率:110mW;安装方式:-;")
      (fields (field (name "Manufacturer") "EVERLIGHT(亿光)"))
      (libsource (lib "easyedapro") (part "19-217/GHC-YR1S2/3T"))
    )
    (comp (ref "P2")
      (value "WJ500V-5.08-2P")
      (footprint "easyedapro:CONN-TH_2P-P5.00_WJ500V-5.08-2P")
      (fields (field (name "Manufacturer") "KANGNEX(康奈克斯电气)"))
      (libsource (lib "easyedapro") (part "WJ500V-5.08-2P-14-00A"))
    )
    (comp (ref "R16")
      (value "10kΩ")
      (footprint "easyedapro:R0603")
      (description "电阻类型:厚膜电阻;阻值:10kΩ;精度:±1%;功率:100mW;")
      (fields
        (field (name "Manufacturer Part") "0603WAF1002T5E")
        (field (name "Manufacturer") "UNI-ROYAL(厚声)")
      )
      (libsource (lib "easyedapro") (part "0603WAF1002T5E"))
    )
    (comp (ref "U3")
      (value "L7805CD2T-TR")
      (footprint "easyedapro:TO-263-2_L10.0-W9.1-P5.08-LS15.2-TL")
      (description "输出类型:固定;输出极性:正;最大输入电压:35V;输出电压:5V;输出电流:1.5A;电源纹波抑制比(PSRR):62dB@(120Hz);")
      (fields (field (name "Manufacturer") "ST(意法半导体)"))
      (libsource (lib "easyedapro") (part "L7805CD2T-TR"))
    )
    (comp (ref "U8")
      (value "REF5050AIDR")
      (footprint "easyedapro:SOIC-8_L5.0-W4.0-P1.27-LS6.0-BL")
      (description "输出类型:固定;输入电压:5.2V~18V;输出电压:5V;输出电流:10mA;精度:±0.1%;")
      (fields (field (name "Manufacturer") "TI(德州仪器)"))
      (libsource (lib "easyedapro") (part "REF5050AIDR"))
    )
    (comp (ref "C5")
      (value "22pF")
      (footprint "easyedapro:C0603")
      (description "容值:22pF;精度:±5%;额定电压:50V;材质(温度系数):C0G;")
      (fields
        (field (name "Manufacturer Part") "CL10C220JB8NNNC")
        (field (name "Manufacturer") "SAMSUNG(三星)")
      )
      (libsource (lib "easyedapro") (part "CL10C220JB8NNNC"))
    )
    (comp (ref "C6")
      (value "22pF")
      (footprint "easyedapro:C0603")
      (description "容值:22pF;精度:±5%;额定电压:50V;材质(温度系数):C0G;")
      (fields
        (field (name "Manufacturer Part") "CL10C220JB8NNNC")
        (field (name "Manufacturer") "SAMSUNG(三星)")
      )
      (libsource (lib "easyedapro") (part "CL10C220JB8NNNC"))
    )
    (comp (ref "C7")
      (value "100nF")
      (footprint "easyedapro:C0603")
      (description "容值:100nF;精度:±10%;额定电压:50V;材质(温度系数):X7R;")
      (fields
        (field (name "Manufacturer Part") "CC0603KRX7R9BB104")
        (field (name "Manufacturer") "YAGEO(国巨)")
      )
      (libsource (lib "easyedapro") (part "CC0603KRX7R9BB104"))
    )
    (comp (ref "C8")
      (value "10uF")
      (footprint "easyedapro:C0603")
      (description "容值:10uF;精度:±10%;额定电压:10V;材质(温度系数):X5R;")
      (fields
        (field (name "Manufacturer Part") "CL10A106KP8NNNC")
        (field (name "Manufacturer") "SAMSUNG(三星)")
      )
      (libsource (lib "easyedapro") (part "CL10A106KP8NNNC"))
    )
    (comp (ref "C9")
      (value "100nF")
      (footprint "easyedapro:C0603")
      (description "容值:100nF;精度:±10%;额定电压:50V;材质(温度系数):X7R;")
      (fields
        (field (name "Manufacturer Part") "CC0603KRX7R9BB104")
        (field (name "Manufacturer") "YAGEO(国巨)")
      )
      (libsource (lib "easyedapro") (part "CC0603KRX7R9BB104"))
    )
    (comp (ref "D2")
      (value "SMAJ5.0A")
      (footprint "easyedapro:SMA_L4.3-W2.6-LS5.0-RD")
      (description "反向截止电压(Vrwm):5V;击穿电压:6.4V;最大钳位电压:9.2V;")
      (fields (field (name "Manufacturer") "Liown(里阳半导体)"))
      (libsource (lib "easyedapro") (part "SMAJ5.0A_C2925443"))
    )
    (comp (ref "D3")
      (value "1N5819WS")
      (footprint "easyedapro:SOD-323_L1.8-W1.3-LS2.5-RD")
      (description "直流反向耐压(Vr):40V;平均整流电流(Io):1A;正向压降(Vf):600mV@1A;")
      (fields (field (name "Manufacturer") "Hottech(合科泰)"))
      (libsource (lib "easyedapro") (part "1N5819WS"))
    )
    (comp (ref "D13")
      (value "1N5819WS")
      (footprint "easyedapro:SOD-323_L1.8-W1.3-LS2.5-RD")
      (description "直流反向耐压(Vr):40V;平均整流电流(Io):1A;正向压降(Vf):600mV@1A;")
      (fields (field (name "Manufacturer") "Hottech(合科泰)"))
      (libsource (lib "easyedapro") (part "1N5819WS"))
    )
    (comp (ref "U4")
      (value "CH340G")
      (footprint "easyedapro:SOIC-16_L9.9-W3.9-P1.27-LS6.0-BL")
      (description "应用功能:收发器;接口协议:USB 2.0;数据速率:2Mbps;")
      (fields (field (name "Manufacturer") "WCH(南京沁恒)"))
      (libsource (lib "easyedapro") (part "CH340G"))
    )
    (comp (ref "USB1")
      (value "USB-B10-BRW")
      (footprint "easyedapro:USB-B-TH_USB-B10-BRW")
      (fields (field (name "Manufacturer") "XUNPU(讯普)"))
      (libsource (lib "easyedapro") (part "USB-B10-BRW"))
    )
    (comp (ref "X2")
      (value "12MHz")
      (footprint "easyedapro:HC-49US_L11.5-W4.5-P4.88")
      (description "频率:12MHz;频率公差:±20ppm;负载电容:20pF;")
      (fields (field (name "Manufacturer Part") "X49SD12MSD2SC") (field (name "Manufacturer") "YXC(扬兴晶振)"))
      (libsource (lib "easyedapro") (part "X49SD12MSD2SC"))
    )
    (comp (ref "J2")
      (value "~")
      (footprint "easyedapro:DEMO板安装孔")
      (libsource (lib "easyedapro") (part "螺孔_3.1X6MM"))
    )
    (comp (ref "J3")
      (value "~")
      (footprint "easyedapro:DEMO板安装孔")
      (libsource (lib "easyedapro") (part "螺孔_3.1X6MM"))
    )
    (comp (ref "J4")
      (value "~")
      (footprint "easyedapro:DEMO板安装孔")
      (libsource (lib "easyedapro") (part "螺孔_3.1X6MM"))
    )
    (comp (ref "J5")
      (value "~")
      (footprint "easyedapro:DEMO板安装孔")
      (libsource (lib "easyedapro") (part "螺孔_3.1X6MM"))
    )
    (comp (ref "C10")
      (value "10uF")
      (footprint "easyedapro:C0603")
      (description "容值:10uF;精度:±20%;额定电压:25V;材质(温度系数):X5R;")
      (fields
        (field (name "Manufacturer Part") "CL10A106MA8NRNC")
        (field (name "Manufacturer") "SAMSUNG(三星)")
      )
      (libsource (lib "easyedapro") (part "CL10A106MA8NRNC"))
    )
    (comp (ref "C11")
      (value "100nF")
      (footprint "easyedapro:C0603")
      (description "容值:100nF;精度:±10%;额定电压:50V;材质(温度系数):X7R;")
      (fields
        (field (name "Manufacturer Part") "CC0603KRX7R9BB104")
        (field (name "Manufacturer") "YAGEO(国巨)")
      )
      (libsource (lib "easyedapro") (part "CC0603KRX7R9BB104"))
    )
    (comp (ref "C12")
      (value "10uF")
      (footprint "easyedapro:C0603")
      (description "容值:10uF;精度:±20%;额定电压:25V;材质(温度系数):X5R;")
      (fields
        (field (name "Manufacturer Part") "CL10A106MA8NRNC")
        (field (name "Manufacturer") "SAMSUNG(三星)")
      )
      (libsource (lib "easyedapro") (part "CL10A106MA8NRNC"))
    )
    (comp (ref "C13")
      (value "100nF")
      (footprint "easyedapro:C0603")
      (description "容值:100nF;精度:±10%;额定电压:50V;材质(温度系数):X7R;")
      (fields
        (field (name "Manufacturer Part") "CC0603KRX7R9BB104")
        (field (name "Manufacturer") "YAGEO(国巨)")
      )
      (libsource (lib "easyedapro") (part "CC0603KRX7R9BB104"))
    )
    (comp (ref "C14")
      (value "100nF")
      (footprint "easyedapro:C0603")
      (description "容值:100nF;精度:±10%;额定电压:50V;材质(温度系数):X7R;")
      (fields
        (field (name "Manufacturer Part") "CC0603KRX7R9BB104")
        (field (name "Manufacturer") "YAGEO(国巨)")
      )
      (libsource (lib "easyedapro") (part "CC0603KRX7R9BB104"))
    )
    (comp (ref "C34")
      (value "10uF")
      (footprint "easyedapro:C0603")
      (description "容值:10uF;精度:±20%;额定电压:25V;材质(温度系数):X5R;")
      (fields
        (field (name "Manufacturer Part") "CL10A106MA8NRNC")
        (field (name "Manufacturer") "SAMSUNG(三星)")
      )
      (libsource (lib "easyedapro") (part "CL10A106MA8NRNC"))
    )
    (comp (ref "C35")
      (value "100nF")
      (footprint "easyedapro:C0603")
      (description "容值:100nF;精度:±10%;额定电压:50V;材质(温度系数):X7R;")
      (fields
        (field (name "Manufacturer Part") "CC0603KRX7R9BB104")
        (field (name "Manufacturer") "YAGEO(国巨)")
      )
      (libsource (lib "easyedapro") (part "CC0603KRX7R9BB104"))
    )
    (comp (ref "C36")
      (value "100nF")
      (footprint "easyedapro:C0603")
      (description "容值:100nF;精度:±10%;额定电压:50V;材质(温度系数):X7R;")
      (fields
        (field (name "Manufacturer Part") "CC0603KRX7R9BB104")
        (field (name "Manufacturer") "YAGEO(国巨)")
      )
      (libsource (lib "easyedapro") (part "CC0603KRX7R9BB104"))
    )
    (comp (ref "C37")
      (value "47uF")
      (footprint "easyedapro:C1206")
      (description "容值:47uF;精度:±20%;额定电压:10V;材质(温度系数):X5R;")
      (fields
        (field (name "Manufacturer Part") "CL31A476MPHNNNE")
        (field (name "Manufacturer") "SAMSUNG(三星)")
      )
      (libsource (lib "easyedapro") (part "CL31A476MPHNNNE"))
    )
    (comp (ref "C38")
      (value "47uF")
      (footprint "easyedapro:C1206")
      (description "容值:47uF;精度:±20%;额定电压:10V;材质(温度系数):X5R;")
      (fields
        (field (name "Manufacturer Part") "CL31A476MPHNNNE")
        (field (name "Manufacturer") "SAMSUNG(三星)")
      )
      (libsource (lib "easyedapro") (part "CL31A476MPHNNNE"))
    )
    (comp (ref "C39")
      (value "100uF")
      (footprint "easyedapro:C1206")
      (description "容值:100uF;精度:±20%;额定电压:6.3V;材质(温度系数):X5R;")
      (fields
        (field (name "Manufacturer Part") "CL31A107MQHNNNE")
        (field (name "Manufacturer") "SAMSUNG(三星)")
      )
      (libsource (lib "easyedapro") (part "CL31A107MQHNNNE"))
    )
    (comp (ref "C40")
      (value "100uF")
      (footprint "easyedapro:C1206")
      (description "容值:100uF;精度:±20%;额定电压:6.3V;材质(温度系数):X5R;")
      (fields
        (field (name "Manufacturer Part") "CL31A107MQHNNNE")
        (field (name "Manufacturer") "SAMSUNG(三星)")
      )
      (libsource (lib "easyedapro") (part "CL31A107MQHNNNE"))
    )
    (comp (ref "C41")
      (value "10uF")
      (footprint "easyedapro:C0805")
      (description "容值:10uF;精度:±10%;额定电压:25V;材质(温度系数):X5R;")
      (fields
        (field (name "Manufacturer Part") "CL21A106KAYNNNE")
        (field (name "Manufacturer") "SAMSUNG(三星)")
      )
      (libsource (lib "easyedapro") (part "CL21A106KAYNNNE"))
    )
    (comp (ref "C42")
      (value "10uF")
      (footprint "easyedapro:C0805")
      (description "容值:10uF;精度:±10%;额定电压:25V;材质(温度系数):X5R;")
      (fields
        (field (name "Manufacturer Part") "CL21A106KAYNNNE")
        (field (name "Manufacturer") "SAMSUNG(三星)")
      )
      (libsource (lib "easyedapro") (part "CL21A106KAYNNNE"))
    )
    (comp (ref "C43")
      (value "100nF")
      (footprint "easyedapro:C0603")
      (description "容值:100nF;精度:±10%;额定电压:50V;材质(温度系数):X7R;")
      (fields
        (field (name "Manufacturer Part") "CC0603KRX7R9BB104")
        (field (name "Manufacturer") "YAGEO(国巨)")
      )
      (libsource (lib "easyedapro") (part "CC0603KRX7R9BB104"))
    )
    (comp (ref "C44")
      (value "100nF")
      (footprint "easyedapro:C0603")
      (description "容值:100nF;精度:±10%;额定电压:50V;材质(温度系数):X7R;")
      (fields
        (field (name "Manufacturer Part") "CC0603KRX7R9BB104")
        (field (name "Manufacturer") "YAGEO(国巨)")
      )
      (libsource (lib "easyedapro") (part "CC0603KRX7R9BB104"))
    )
    (comp (ref "C47")
      (value "10uF")
      (footprint "easyedapro:C0603")
      (description "容值:10uF;精度:±20%;额定电压:25V;材质(温度系数):X5R;")
      (fields
        (field (name "Manufacturer Part") "CL10A106MA8NRNC")
        (field (name "Manufacturer") "SAMSUNG(三星)")
      )
      (libsource (lib "easyedapro") (part "CL10A106MA8NRNC"))
    )
    (comp (ref "C48")
      (value "100nF")
      (footprint "easyedapro:C0603")
      (description "容值:100nF;精度:±10%;额定电压:50V;材质(温度系数):X7R;")
      (fields
        (field (name "Manufacturer Part") "CC0603KRX7R9BB104")
        (field (name "Manufacturer") "YAGEO(国巨)")
      )
      (libsource (lib "easyedapro") (part "CC0603KRX7R9BB104"))
    )
    (comp (ref "H2")
      (value "PZ254V-11-01P")
      (footprint "easyedapro:HDR-TH_1P-P2.54-V-M")
      (fields (field (name "Manufacturer") "XFCN(兴飞)"))
      (libsource (lib "easyedapro") (part "PZ254V-11-01P"))
    )
    (comp (ref "H3")
      (value "PZ254V-11-01P")
      (footprint "easyedapro:HDR-TH_1P-P2.54-V-M")
      (fields (field (name "Manufacturer") "XFCN(兴飞)"))
      (libsource (lib "easyedapro") (part "PZ254V-11-01P"))
    )
    (comp (ref "H6")
      (value "PZ254V-11-01P")
      (footprint "easyedapro:HDR-TH_1P-P2.54-V-M")
      (fields (field (name "Manufacturer") "XFCN(兴飞)"))
      (libsource (lib "easyedapro") (part "PZ254V-11-01P"))
    )
    (comp (ref "H7")
      (value "PZ254V-11-01P")
      (footprint "easyedapro:HDR-TH_1P-P2.54-V-M")
      (fields (field (name "Manufacturer") "XFCN(兴飞)"))
      (libsource (lib "easyedapro") (part "PZ254V-11-01P"))
    )
    (comp (ref "L1")
      (value "10uH")
      (footprint "easyedapro:IND-SMD_L2.5-W1.8")
      (description "电感值:10uH;精度:±20%;饱和电流(Isat):480mA;")
      (fields
        (field (name "Manufacturer Part") "CBC2518T100M")
        (field (name "Manufacturer") "TAIYO YUDEN(太诱)")
      )
      (libsource (lib "easyedapro") (part "CBC2518T100M"))
    )
    (comp (ref "R4")
      (value "22Ω")
      (footprint "easyedapro:R0603")
      (description "电阻类型:厚膜电阻;阻值:22Ω;精度:±1%;功率:100mW;")
      (fields
        (field (name "Manufacturer Part") "0603WAF220JT5E")
        (field (name "Manufacturer") "UNI-ROYAL(厚声)")
      )
      (libsource (lib "easyedapro") (part "0603WAF220JT5E"))
    )
    (comp (ref "R17")
      (value "10mΩ")
      (footprint "easyedapro:RES-SMD_L6.4-W3.2-R2512")
      (description "阻值:10mΩ;功率:3W;")
      (fields
        (field (name "Manufacturer Part") "HoJLR2512-3W-10mR-1%")
        (field (name "Manufacturer") "Milliohm(毫欧)")
      )
      (libsource (lib "easyedapro") (part "HOJLR2512-3W-10MR-1%"))
    )
    (comp (ref "U5")
      (value "AD5541ARZ-REEL7")
      (footprint "easyedapro:SOIC-8_L5.0-W4.0-P1.27-LS6.0-BL")
      (description "D/A 位数:-;D/A通道数:-;输出类型:-;读写接口类型:-;")
      (fields (field (name "Manufacturer") "ADI(亚德诺)/LINEAR"))
      (libsource (lib "easyedapro") (part "AD5541ARZ-REEL7"))
    )
    (comp (ref "U7")
      (value "OPA2350UA/2K5")
      (footprint "easyedapro:SOIC-8_L4.9-W3.9-P1.27-LS6.0-BL")
      (description "放大器组数:2;输入偏置电流(Ib):0.5pA;增益带宽积(GBP):38MHz;压摆率(SR):22V/us;轨到轨:轨到轨;")
      (fields (field (name "Manufacturer") "TI(德州仪器)"))
      (libsource (lib "easyedapro") (part "OPA2350UA/2K5"))
    )
    (comp (ref "U40")
      (value "RH-5000")
      (footprint "easyedapro:TEST-TH_BD2.54-P1.4_RED")
      (description "100x80mm")
      (fields (field (name "Manufacturer") "荣和"))
      (libsource (lib "easyedapro") (part "RH-5000"))
    )
    (comp (ref "U41")
      (value "OPA548F/500")
      (footprint "easyedapro:TO-263-7_L10.2-W10.4-P1.27-LS14.4-TL")
      (description "放大器组数:1;带宽(-3db):-;输入偏置电流(Ib):100nA;增益带宽积(GBP):1MHz;压摆率(SR):10V/us;")
      (fields (field (name "Manufacturer") "TI(德州仪器)"))
      (libsource (lib "easyedapro") (part "OPA548F/500"))
    )
    (comp (ref "U43")
      (value "DB136HB-10.16-1P-S")
      (footprint "easyedapro:CONN-TH_DIBO_DB136HB-10.16-1P-S")
      (fields (field (name "Manufacturer") "DIBO(地博电气)"))
      (libsource (lib "easyedapro") (part "DB136HB-10.16-1P-S"))
    )
    (comp (ref "U44")
      (value "DB136HB-10.16-1P-S")
      (footprint "easyedapro:CONN-TH_DIBO_DB136HB-10.16-1P-S")
      (fields (field (name "Manufacturer") "DIBO(地博电气)"))
      (libsource (lib "easyedapro") (part "DB136HB-10.16-1P-S"))
    )
    (comp (ref "U45")
      (value "RH-5000")
      (footprint "easyedapro:TEST-TH_BD2.54-P1.4_RED")
      (description "100x80mm")
      (fields (field (name "Manufacturer") "荣和"))
      (libsource (lib "easyedapro") (part "RH-5000"))
    )
    (comp (ref "U47")
      (value "RH-5000")
      (footprint "easyedapro:TEST-TH_BD2.54-P1.4_RED")
      (description "100x80mm")
      (fields (field (name "Manufacturer") "荣和"))
      (libsource (lib "easyedapro") (part "RH-5000"))
    )
    (comp (ref "U48")
      (value "RH-5000")
      (footprint "easyedapro:TEST-TH_BD2.54-P1.4_RED")
      (description "100x80mm")
      (fields (field (name "Manufacturer") "荣和"))
      (libsource (lib "easyedapro") (part "RH-5000"))
    )
    (comp (ref "C26")
      (value "10000uF")
      (footprint "easyedapro:CAP-TH_BD16.0-P7.50-D1.2-FD")
      (description "容值:10000uF;精度:±20%;额定电压:16V;")
      (fields
        (field (name "Manufacturer Part") "KM1C103ML350A00CV0")
        (field (name "Manufacturer") "HUAWEI(华威集团)")
      )
      (libsource (lib "easyedapro") (part "KM1C103ML350A00CV0"))
    )
    (comp (ref "C27")
      (value "10000uF")
      (footprint "easyedapro:CAP-TH_BD16.0-P7.50-D1.2-FD")
      (description "容值:10000uF;精度:±20%;额定电压:16V;")
      (fields
        (field (name "Manufacturer Part") "KM1C103ML350A00CV0")
        (field (name "Manufacturer") "HUAWEI(华威集团)")
      )
      (libsource (lib "easyedapro") (part "KM1C103ML350A00CV0"))
    )
    (comp (ref "C28")
      (value "10000uF")
      (footprint "easyedapro:CAP-TH_BD16.0-P7.50-D1.2-FD")
      (description "容值:10000uF;精度:±20%;额定电压:16V;")
      (fields
        (field (name "Manufacturer Part") "KM1C103ML350A00CV0")
        (field (name "Manufacturer") "HUAWEI(华威集团)")
      )
      (libsource (lib "easyedapro") (part "KM1C103ML350A00CV0"))
    )
    (comp (ref "C29")
      (value "10000uF")
      (footprint "easyedapro:CAP-TH_BD16.0-P7.50-D1.2-FD")
      (description "容值:10000uF;精度:±20%;额定电压:16V;")
      (fields
        (field (name "Manufacturer Part") "KM1C103ML350A00CV0")
        (field (name "Manufacturer") "HUAWEI(华威集团)")
      )
      (libsource (lib "easyedapro") (part "KM1C103ML350A00CV0"))
    )
    (comp (ref "C30")
      (value "10000uF")
      (footprint "easyedapro:CAP-TH_BD16.0-P7.50-D1.2-FD")
      (description "容值:10000uF;精度:±20%;额定电压:16V;")
      (fields
        (field (name "Manufacturer Part") "KM1C103ML350A00CV0")
        (field (name "Manufacturer") "HUAWEI(华威集团)")
      )
      (libsource (lib "easyedapro") (part "KM1C103ML350A00CV0"))
    )
    (comp (ref "C31")
      (value "10000uF")
      (footprint "easyedapro:CAP-TH_BD16.0-P7.50-D1.2-FD")
      (description "容值:10000uF;精度:±20%;额定电压:16V;")
      (fields
        (field (name "Manufacturer Part") "KM1C103ML350A00CV0")
        (field (name "Manufacturer") "HUAWEI(华威集团)")
      )
      (libsource (lib "easyedapro") (part "KM1C103ML350A00CV0"))
    )
    (comp (ref "C32")
      (value "0.1F")
      (footprint "easyedapro:CAP-TH_L10.5-W5.5-P7.0-D1.0")
      (description "容值:0.1F;精度:-20%~+80%;额定电压:5.5V;漏电流:-;等效串联电阻:1.2Ω@1kHz;")
      (fields (field (name "Manufacturer Part") "SP-5R5-Z104VY") (field (name "Manufacturer") "KAMCAP(凯美)"))
      (libsource (lib "easyedapro") (part "SP-5R5-Z104VY"))
    )
    (comp (ref "C33")
      (value "0.1F")
      (footprint "easyedapro:CAP-TH_L10.5-W5.5-P7.0-D1.0")
      (description "容值:0.1F;精度:-20%~+80%;额定电压:5.5V;漏电流:-;等效串联电阻:1.2Ω@1kHz;")
      (fields (field (name "Manufacturer Part") "SP-5R5-Z104VY") (field (name "Manufacturer") "KAMCAP(凯美)"))
      (libsource (lib "easyedapro") (part "SP-5R5-Z104VY"))
    )
    (comp (ref "D4")
      (value "1N4148WS")
      (footprint "easyedapro:SOD-323_L1.8-W1.3-LS2.5-RD")
      (description "二极管配置:独立式;功率:200mW;直流反向耐压(Vr):100V;平均整流电流(Io):150mA;正向压降(Vf):1.25V@150mA;反向恢复时间(trr):4ns;")
      (fields (field (name "Manufacturer") "CJ(江苏长电/长晶)"))
      (libsource (lib "easyedapro") (part "1N4148WS T4"))
    )
    (comp (ref "D5")
      (value "1N4148WS")
      (footprint "easyedapro:SOD-323_L1.8-W1.3-LS2.5-RD")
      (description "二极管配置:独立式;功率:200mW;直流反向耐压(Vr):100V;平均整流电流(Io):150mA;正向压降(Vf):1.25V@150mA;反向恢复时间(trr):4ns;")
      (fields (field (name "Manufacturer") "CJ(江苏长电/长晶)"))
      (libsource (lib "easyedapro") (part "1N4148WS T4"))
    )
    (comp (ref "D6")
      (value "1N4148WS")
      (footprint "easyedapro:SOD-323_L1.8-W1.3-LS2.5-RD")
      (description "二极管配置:独立式;功率:200mW;直流反向耐压(Vr):100V;平均整流电流(Io):150mA;正向压降(Vf):1.25V@150mA;反向恢复时间(trr):4ns;")
      (fields (field (name "Manufacturer") "CJ(江苏长电/长晶)"))
      (libsource (lib "easyedapro") (part "1N4148WS T4"))
    )
    (comp (ref "D7")
      (value "1N4148WS")
      (footprint "easyedapro:SOD-323_L1.8-W1.3-LS2.5-RD")
      (description "二极管配置:独立式;功率:200mW;直流反向耐压(Vr):100V;平均整流电流(Io):150mA;正向压降(Vf):1.25V@150mA;反向恢复时间(trr):4ns;")
      (fields (field (name "Manufacturer") "CJ(江苏长电/长晶)"))
      (libsource (lib "easyedapro") (part "1N4148WS T4"))
    )
    (comp (ref "D8")
      (value "1N4148WS")
      (footprint "easyedapro:SOD-323_L1.8-W1.3-LS2.5-RD")
      (description "二极管配置:独立式;功率:200mW;直流反向耐压(Vr):100V;平均整流电流(Io):150mA;正向压降(Vf):1.25V@150mA;反向恢复时间(trr):4ns;")
      (fields (field (name "Manufacturer") "CJ(江苏长电/长晶)"))
      (libsource (lib "easyedapro") (part "1N4148WS T4"))
    )
    (comp (ref "D9")
      (value "1N4148WS")
      (footprint "easyedapro:SOD-323_L1.8-W1.3-LS2.5-RD")
      (description "二极管配置:独立式;功率:200mW;直流反向耐压(Vr):100V;平均整流电流(Io):150mA;正向压降(Vf):1.25V@150mA;反向恢复时间(trr):4ns;")
      (fields (field (name "Manufacturer") "CJ(江苏长电/长晶)"))
      (libsource (lib "easyedapro") (part "1N4148WS T4"))
    )
    (comp (ref "D10")
      (value "1N4148WS")
      (footprint "easyedapro:SOD-323_L1.8-W1.3-LS2.5-RD")
      (description "二极管配置:独立式;功率:200mW;直流反向耐压(Vr):100V;平均整流电流(Io):150mA;正向压降(Vf):1.25V@150mA;反向恢复时间(trr):4ns;")
      (fields (field (name "Manufacturer") "CJ(江苏长电/长晶)"))
      (libsource (lib "easyedapro") (part "1N4148WS T4"))
    )
    (comp (ref "D11")
      (value "1N4148WS")
      (footprint "easyedapro:SOD-323_L1.8-W1.3-LS2.5-RD")
      (description "二极管配置:独立式;功率:200mW;直流反向耐压(Vr):100V;平均整流电流(Io):150mA;正向压降(Vf):1.25V@150mA;反向恢复时间(trr):4ns;")
      (fields (field (name "Manufacturer") "CJ(江苏长电/长晶)"))
      (libsource (lib "easyedapro") (part "1N4148WS T4"))
    )
    (comp (ref "D12")
      (value "1N4148WS")
      (footprint "easyedapro:SOD-323_L1.8-W1.3-LS2.5-RD")
      (description "二极管配置:独立式;功率:200mW;直流反向耐压(Vr):100V;平均整流电流(Io):150mA;正向压降(Vf):1.25V@150mA;反向恢复时间(trr):4ns;")
      (fields (field (name "Manufacturer") "CJ(江苏长电/长晶)"))
      (libsource (lib "easyedapro") (part "1N4148WS T4"))
    )
    (comp (ref "H1")
      (value "PZ254V-11-02P")
      (footprint "easyedapro:HDR-TH_2P-P2.54-V-M")
      (fields (field (name "Manufacturer") "XFCN(兴飞)"))
      (libsource (lib "easyedapro") (part "PZ254V-11-02P"))
    )
    (comp (ref "H4")
      (value "PZ254V-11-01P")
      (footprint "easyedapro:HDR-TH_1P-P2.54-V-M")
      (fields (field (name "Manufacturer") "XFCN(兴飞)"))
      (libsource (lib "easyedapro") (part "PZ254V-11-01P"))
    )
    (comp (ref "H5")
      (value "PZ254V-11-01P")
      (footprint "easyedapro:HDR-TH_1P-P2.54-V-M")
      (fields (field (name "Manufacturer") "XFCN(兴飞)"))
      (libsource (lib "easyedapro") (part "PZ254V-11-01P"))
    )
    (comp (ref "K1")
      (value "HF49FD/005-1H11")
      (footprint "easyedapro:RELAY-TH_HF49FD-XXX-1H11-XXX")
      (description "线圈电压:5V;引脚数:4;触点形式:一组常开:1A(单刀单掷-常开);触点容量(电阻负载):5A@30VDC；5A@250VAC;触点材料:AgNi;")
      (fields (field (name "Manufacturer") "HF(宏发)"))
      (libsource (lib "easyedapro") (part "HF49FD/005-1H11"))
    )
    (comp (ref "K2")
      (value "HF49FD/005-1H11")
      (footprint "easyedapro:RELAY-TH_HF49FD-XXX-1H11-XXX")
      (description "线圈电压:5V;引脚数:4;触点形式:一组常开:1A(单刀单掷-常开);触点容量(电阻负载):5A@30VDC；5A@250VAC;触点材料:AgNi;")
      (fields (field (name "Manufacturer") "HF(宏发)"))
      (libsource (lib "easyedapro") (part "HF49FD/005-1H11"))
    )
    (comp (ref "K3")
      (value "HF49FD/005-1H11")
      (footprint "easyedapro:RELAY-TH_HF49FD-XXX-1H11-XXX")
      (description "线圈电压:5V;引脚数:4;触点形式:一组常开:1A(单刀单掷-常开);触点容量(电阻负载):5A@30VDC；5A@250VAC;触点材料:AgNi;")
      (fields (field (name "Manufacturer") "HF(宏发)"))
      (libsource (lib "easyedapro") (part "HF49FD/005-1H11"))
    )
    (comp (ref "K4")
      (value "HF49FD/005-1H11")
      (footprint "easyedapro:RELAY-TH_HF49FD-XXX-1H11-XXX")
      (description "线圈电压:5V;引脚数:4;触点形式:一组常开:1A(单刀单掷-常开);触点容量(电阻负载):5A@30VDC；5A@250VAC;触点材料:AgNi;")
      (fields (field (name "Manufacturer") "HF(宏发)"))
      (libsource (lib "easyedapro") (part "HF49FD/005-1H11"))
    )
    (comp (ref "K5")
      (value "HF49FD/005-1H11")
      (footprint "easyedapro:RELAY-TH_HF49FD-XXX-1H11-XXX")
      (description "线圈电压:5V;引脚数:4;触点形式:一组常开:1A(单刀单掷-常开);触点容量(电阻负载):5A@30VDC；5A@250VAC;触点材料:AgNi;")
      (fields (field (name "Manufacturer") "HF(宏发)"))
      (libsource (lib "easyedapro") (part "HF49FD/005-1H11"))
    )
    (comp (ref "K6")
      (value "HF49FD/005-1H11")
      (footprint "easyedapro:RELAY-TH_HF49FD-XXX-1H11-XXX")
      (description "线圈电压:5V;引脚数:4;触点形式:一组常开:1A(单刀单掷-常开);触点容量(电阻负载):5A@30VDC；5A@250VAC;触点材料:AgNi;")
      (fields (field (name "Manufacturer") "HF(宏发)"))
      (libsource (lib "easyedapro") (part "HF49FD/005-1H11"))
    )
    (comp (ref "K7")
      (value "HF49FD/005-1H11")
      (footprint "easyedapro:RELAY-TH_HF49FD-XXX-1H11-XXX")
      (description "线圈电压:5V;引脚数:4;触点形式:一组常开:1A(单刀单掷-常开);触点容量(电阻负载):5A@30VDC；5A@250VAC;触点材料:AgNi;")
      (fields (field (name "Manufacturer") "HF(宏发)"))
      (libsource (lib "easyedapro") (part "HF49FD/005-1H11"))
    )
    (comp (ref "K8")
      (value "HF49FD/005-1H11")
      (footprint "easyedapro:RELAY-TH_HF49FD-XXX-1H11-XXX")
      (description "线圈电压:5V;引脚数:4;触点形式:一组常开:1A(单刀单掷-常开);触点容量(电阻负载):5A@30VDC；5A@250VAC;触点材料:AgNi;")
      (fields (field (name "Manufacturer") "HF(宏发)"))
      (libsource (lib "easyedapro") (part "HF49FD/005-1H11"))
    )
    (comp (ref "K9")
      (value "HF49FD/005-1H11")
      (footprint "easyedapro:RELAY-TH_HF49FD-XXX-1H11-XXX")
      (description "线圈电压:5V;引脚数:4;触点形式:一组常开:1A(单刀单掷-常开);触点容量(电阻负载):5A@30VDC；5A@250VAC;触点材料:AgNi;")
      (fields (field (name "Manufacturer") "HF(宏发)"))
      (libsource (lib "easyedapro") (part "HF49FD/005-1H11"))
    )
    (comp (ref "LED4")
      (value "19-217/GHC-YR1S2/3T")
      (footprint "easyedapro:LED0603-RD")
      (description "发光颜色:翠绿;二极管配置:-;主波长:520nm~535nm;色温:-;功率:110mW;安装方式:-;")
      (fields (field (name "Manufacturer") "EVERLIGHT(亿光)"))
      (libsource (lib "easyedapro") (part "19-217/GHC-YR1S2/3T"))
    )
    (comp (ref "LED5")
      (value "19-217/GHC-YR1S2/3T")
      (footprint "easyedapro:LED0603-RD")
      (description "发光颜色:翠绿;二极管配置:-;主波长:520nm~535nm;色温:-;功率:110mW;安装方式:-;")
      (fields (field (name "Manufacturer") "EVERLIGHT(亿光)"))
      (libsource (lib "easyedapro") (part "19-217/GHC-YR1S2/3T"))
    )
    (comp (ref "LED6")
      (value "19-217/GHC-YR1S2/3T")
      (footprint "easyedapro:LED0603-RD")
      (description "发光颜色:翠绿;二极管配置:-;主波长:520nm~535nm;色温:-;功率:110mW;安装方式:-;")
      (fields (field (name "Manufacturer") "EVERLIGHT(亿光)"))
      (libsource (lib "easyedapro") (part "19-217/GHC-YR1S2/3T"))
    )
    (comp (ref "LED7")
      (value "19-217/GHC-YR1S2/3T")
      (footprint "easyedapro:LED0603-RD")
      (description "发光颜色:翠绿;二极管配置:-;主波长:520nm~535nm;色温:-;功率:110mW;安装方式:-;")
      (fields (field (name "Manufacturer") "EVERLIGHT(亿光)"))
      (libsource (lib "easyedapro") (part "19-217/GHC-YR1S2/3T"))
    )
    (comp (ref "LED8")
      (value "19-217/GHC-YR1S2/3T")
      (footprint "easyedapro:LED0603-RD")
      (description "发光颜色:翠绿;二极管配置:-;主波长:520nm~535nm;色温:-;功率:110mW;安装方式:-;")
      (fields (field (name "Manufacturer") "EVERLIGHT(亿光)"))
      (libsource (lib "easyedapro") (part "19-217/GHC-YR1S2/3T"))
    )
    (comp (ref "LED9")
      (value "19-217/GHC-YR1S2/3T")
      (footprint "easyedapro:LED0603-RD")
      (description "发光颜色:翠绿;二极管配置:-;主波长:520nm~535nm;色温:-;功率:110mW;安装方式:-;")
      (fields (field (name "Manufacturer") "EVERLIGHT(亿光)"))
      (libsource (lib "easyedapro") (part "19-217/GHC-YR1S2/3T"))
    )
    (comp (ref "LED10")
      (value "19-217/GHC-YR1S2/3T")
      (footprint "easyedapro:LED0603-RD")
      (description "发光颜色:翠绿;二极管配置:-;主波长:520nm~535nm;色温:-;功率:110mW;安装方式:-;")
      (fields (field (name "Manufacturer") "EVERLIGHT(亿光)"))
      (libsource (lib "easyedapro") (part "19-217/GHC-YR1S2/3T"))
    )
    (comp (ref "LED11")
      (value "19-217/GHC-YR1S2/3T")
      (footprint "easyedapro:LED0603-RD")
      (description "发光颜色:翠绿;二极管配置:-;主波长:520nm~535nm;色温:-;功率:110mW;安装方式:-;")
      (fields (field (name "Manufacturer") "EVERLIGHT(亿光)"))
      (libsource (lib "easyedapro") (part "19-217/GHC-YR1S2/3T"))
    )
    (comp (ref "LED12")
      (value "19-217/GHC-YR1S2/3T")
      (footprint "easyedapro:LED0603-RD")
      (description "发光颜色:翠绿;二极管配置:-;主波长:520nm~535nm;色温:-;功率:110mW;安装方式:-;")
      (fields (field (name "Manufacturer") "EVERLIGHT(亿光)"))
      (libsource (lib "easyedapro") (part "19-217/GHC-YR1S2/3T"))
    )
    (comp (ref "Q1")
      (value "SS8050")
      (footprint "easyedapro:SOT-23-3_L2.9-W1.3-P1.90-LS2.4-BR")
      (description "晶体管类型:NPN;集射极击穿电压(Vceo):25V;集电极电流(Ic):1.5A;功率(Pd):300mW;直流电流增益(hFE@Ic,Vce):200@100mA,1V;")
      (fields (field (name "Manufacturer") "CJ(江苏长电/长晶)"))
      (libsource (lib "easyedapro") (part "SS8050_C2150"))
    )
    (comp (ref "Q2")
      (value "SS8050")
      (footprint "easyedapro:SOT-23-3_L2.9-W1.3-P1.90-LS2.4-BR")
      (description "晶体管类型:NPN;集射极击穿电压(Vceo):25V;集电极电流(Ic):1.5A;功率(Pd):300mW;直流电流增益(hFE@Ic,Vce):200@100mA,1V;")
      (fields (field (name "Manufacturer") "CJ(江苏长电/长晶)"))
      (libsource (lib "easyedapro") (part "SS8050_C2150"))
    )
    (comp (ref "Q3")
      (value "SS8050")
      (footprint "easyedapro:SOT-23-3_L2.9-W1.3-P1.90-LS2.4-BR")
      (description "晶体管类型:NPN;集射极击穿电压(Vceo):25V;集电极电流(Ic):1.5A;功率(Pd):300mW;直流电流增益(hFE@Ic,Vce):200@100mA,1V;")
      (fields (field (name "Manufacturer") "CJ(江苏长电/长晶)"))
      (libsource (lib "easyedapro") (part "SS8050_C2150"))
    )
    (comp (ref "Q4")
      (value "SS8050")
      (footprint "easyedapro:SOT-23-3_L2.9-W1.3-P1.90-LS2.4-BR")
      (description "晶体管类型:NPN;集射极击穿电压(Vceo):25V;集电极电流(Ic):1.5A;功率(Pd):300mW;直流电流增益(hFE@Ic,Vce):200@100mA,1V;")
      (fields (field (name "Manufacturer") "CJ(江苏长电/长晶)"))
      (libsource (lib "easyedapro") (part "SS8050_C2150"))
    )
    (comp (ref "Q5")
      (value "SS8050")
      (footprint "easyedapro:SOT-23-3_L2.9-W1.3-P1.90-LS2.4-BR")
      (description "晶体管类型:NPN;集射极击穿电压(Vceo):25V;集电极电流(Ic):1.5A;功率(Pd):300mW;直流电流增益(hFE@Ic,Vce):200@100mA,1V;")
      (fields (field (name "Manufacturer") "CJ(江苏长电/长晶)"))
      (libsource (lib "easyedapro") (part "SS8050_C2150"))
    )
    (comp (ref "Q6")
      (value "SS8050")
      (footprint "easyedapro:SOT-23-3_L2.9-W1.3-P1.90-LS2.4-BR")
      (description "晶体管类型:NPN;集射极击穿电压(Vceo):25V;集电极电流(Ic):1.5A;功率(Pd):300mW;直流电流增益(hFE@Ic,Vce):200@100mA,1V;")
      (fields (field (name "Manufacturer") "CJ(江苏长电/长晶)"))
      (libsource (lib "easyedapro") (part "SS8050_C2150"))
    )
    (comp (ref "Q7")
      (value "SS8050")
      (footprint "easyedapro:SOT-23-3_L2.9-W1.3-P1.90-LS2.4-BR")
      (description "晶体管类型:NPN;集射极击穿电压(Vceo):25V;集电极电流(Ic):1.5A;功率(Pd):300mW;直流电流增益(hFE@Ic,Vce):200@100mA,1V;")
      (fields (field (name "Manufacturer") "CJ(江苏长电/长晶)"))
      (libsource (lib "easyedapro") (part "SS8050_C2150"))
    )
    (comp (ref "Q8")
      (value "SS8050")
      (footprint "easyedapro:SOT-23-3_L2.9-W1.3-P1.90-LS2.4-BR")
      (description "晶体管类型:NPN;集射极击穿电压(Vceo):25V;集电极电流(Ic):1.5A;功率(Pd):300mW;直流电流增益(hFE@Ic,Vce):200@100mA,1V;")
      (fields (field (name "Manufacturer") "CJ(江苏长电/长晶)"))
      (libsource (lib "easyedapro") (part "SS8050_C2150"))
    )
    (comp (ref "Q9")
      (value "SS8050")
      (footprint "easyedapro:SOT-23-3_L2.9-W1.3-P1.90-LS2.4-BR")
      (description "晶体管类型:NPN;集射极击穿电压(Vceo):25V;集电极电流(Ic):1.5A;功率(Pd):300mW;直流电流增益(hFE@Ic,Vce):200@100mA,1V;")
      (fields (field (name "Manufacturer") "CJ(江苏长电/长晶)"))
      (libsource (lib "easyedapro") (part "SS8050_C2150"))
    )
    (comp (ref "R5")
      (value "10kΩ")
      (footprint "easyedapro:R0603")
      (description "电阻类型:厚膜电阻;阻值:10kΩ;精度:±1%;功率:100mW;")
      (fields
        (field (name "Manufacturer Part") "0603WAF1002T5E")
        (field (name "Manufacturer") "UNI-ROYAL(厚声)")
      )
      (libsource (lib "easyedapro") (part "0603WAF1002T5E"))
    )
    (comp (ref "R6")
      (value "10kΩ")
      (footprint "easyedapro:R0603")
      (description "电阻类型:厚膜电阻;阻值:10kΩ;精度:±1%;功率:100mW;")
      (fields
        (field (name "Manufacturer Part") "0603WAF1002T5E")
        (field (name "Manufacturer") "UNI-ROYAL(厚声)")
      )
      (libsource (lib "easyedapro") (part "0603WAF1002T5E"))
    )
    (comp (ref "R7")
      (value "10kΩ")
      (footprint "easyedapro:R0603")
      (description "电阻类型:厚膜电阻;阻值:10kΩ;精度:±1%;功率:100mW;")
      (fields
        (field (name "Manufacturer Part") "0603WAF1002T5E")
        (field (name "Manufacturer") "UNI-ROYAL(厚声)")
      )
      (libsource (lib "easyedapro") (part "0603WAF1002T5E"))
    )
    (comp (ref "R8")
      (value "10kΩ")
      (footprint "easyedapro:R0603")
      (description "电阻类型:厚膜电阻;阻值:10kΩ;精度:±1%;功率:100mW;")
      (fields
        (field (name "Manufacturer Part") "0603WAF1002T5E")
        (field (name "Manufacturer") "UNI-ROYAL(厚声)")
      )
      (libsource (lib "easyedapro") (part "0603WAF1002T5E"))
    )
    (comp (ref "R9")
      (value "10kΩ")
      (footprint "easyedapro:R0603")
      (description "电阻类型:厚膜电阻;阻值:10kΩ;精度:±1%;功率:100mW;")
      (fields
        (field (name "Manufacturer Part") "0603WAF1002T5E")
        (field (name "Manufacturer") "UNI-ROYAL(厚声)")
      )
      (libsource (lib "easyedapro") (part "0603WAF1002T5E"))
    )
    (comp (ref "R10")
      (value "10kΩ")
      (footprint "easyedapro:R0603")
      (description "电阻类型:厚膜电阻;阻值:10kΩ;精度:±1%;功率:100mW;")
      (fields
        (field (name "Manufacturer Part") "0603WAF1002T5E")
        (field (name "Manufacturer") "UNI-ROYAL(厚声)")
      )
      (libsource (lib "easyedapro") (part "0603WAF1002T5E"))
    )
    (comp (ref "R11")
      (value "10kΩ")
      (footprint "easyedapro:R0603")
      (description "电阻类型:厚膜电阻;阻值:10kΩ;精度:±1%;功率:100mW;")
      (fields
        (field (name "Manufacturer Part") "0603WAF1002T5E")
        (field (name "Manufacturer") "UNI-ROYAL(厚声)")
      )
      (libsource (lib "easyedapro") (part "0603WAF1002T5E"))
    )
    (comp (ref "R12")
      (value "10kΩ")
      (footprint "easyedapro:R0603")
      (description "电阻类型:厚膜电阻;阻值:10kΩ;精度:±1%;功率:100mW;")
      (fields
        (field (name "Manufacturer Part") "0603WAF1002T5E")
        (field (name "Manufacturer") "UNI-ROYAL(厚声)")
      )
      (libsource (lib "easyedapro") (part "0603WAF1002T5E"))
    )
    (comp (ref "R13")
      (value "10kΩ")
      (footprint "easyedapro:R0603")
      (description "电阻类型:厚膜电阻;阻值:10kΩ;精度:±1%;功率:100mW;")
      (fields
        (field (name "Manufacturer Part") "0603WAF1002T5E")
        (field (name "Manufacturer") "UNI-ROYAL(厚声)")
      )
      (libsource (lib "easyedapro") (part "0603WAF1002T5E"))
    )
    (comp (ref "R14")
      (value "0Ω")
      (footprint "easyedapro:R0603")
      (description "电阻类型:厚膜电阻;阻值:0Ω;精度:±1%;功率:100mW;")
      (fields
        (field (name "Manufacturer Part") "0603WAF0000T5E")
        (field (name "Manufacturer") "UNI-ROYAL(厚声)")
      )
      (libsource (lib "easyedapro") (part "0603WAF0000T5E"))
    )
    (comp (ref "R15")
      (value "100Ω")
      (footprint "easyedapro:R0603")
      (description "电阻类型:厚膜电阻;阻值:100Ω;精度:±1%;功率:100mW;")
      (fields (field (name "Manufacturer Part") "RC0603FR-07100RL") (field (name "Manufacturer") "YAGEO(国巨)"))
      (libsource (lib "easyedapro") (part "RC0603FR-07100RL"))
    )
    (comp (ref "U38")
      (value "RH-5000")
      (footprint "easyedapro:TEST-TH_BD2.54-P1.4_RED")
      (description "100x80mm")
      (fields (field (name "Manufacturer") "荣和"))
      (libsource (lib "easyedapro") (part "RH-5000"))
    )
    (comp (ref "U42")
      (value "DB136HB-10.16-1P-S")
      (footprint "easyedapro:CONN-TH_DIBO_DB136HB-10.16-1P-S")
      (fields (field (name "Manufacturer") "DIBO(地博电气)"))
      (libsource (lib "easyedapro") (part "DB136HB-10.16-1P-S"))
    )
    (comp (ref "U46")
      (value "RH-5000")
      (footprint "easyedapro:TEST-TH_BD2.54-P1.4_RED")
      (description "100x80mm")
      (fields (field (name "Manufacturer") "荣和"))
      (libsource (lib "easyedapro") (part "RH-5000"))
    )
  )
  (nets
    (net (code "1") (name "DAC_OUT") (class "Default")
      (node (ref "U5") (pin "1") (pinfunction "VOUT_1") (pintype "input"))
      (node (ref "U7") (pin "5") (pinfunction "IN_B+_5") (pintype "unspecified"))
    )
    (net (code "2") (name "DAC_OUT_VCC") (class "Default")
      (node (ref "C37") (pin "2") (pinfunction "2_2") (pintype "unspecified"))
      (node (ref "C38") (pin "2") (pinfunction "2_2") (pintype "unspecified"))
      (node (ref "C39") (pin "2") (pinfunction "2_2") (pintype "input"))
      (node (ref "C40") (pin "2") (pinfunction "2_2") (pintype "input"))
      (node (ref "C41") (pin "2") (pinfunction "2_2") (pintype "input"))
      (node (ref "C42") (pin "2") (pinfunction "2_2") (pintype "input"))
      (node (ref "C43") (pin "2") (pinfunction "2_2") (pintype "unspecified"))
      (node (ref "C44") (pin "2") (pinfunction "2_2") (pintype "unspecified"))
      (node (ref "H2") (pin "1") (pinfunction "1_1") (pintype "input"))
      (node (ref "H3") (pin "1") (pinfunction "1_1") (pintype "input"))
      (node (ref "L1") (pin "2") (pinfunction "2_2") (pintype "unspecified"))
      (node (ref "U40") (pin "1") (pinfunction "1_1") (pintype "input"))
      (node (ref "U43") (pin "1") (pinfunction "1_1") (pintype "unspecified"))
      (node (ref "U43") (pin "2") (pinfunction "2_2") (pintype "unspecified"))
      (node (ref "U45") (pin "1") (pinfunction "1_1") (pintype "input"))
    )
    (net (code "3") (name "DC_9V") (class "Default")
      (node (ref "C1") (pin "1") (pinfunction "1_1") (pintype "input"))
      (node (ref "C16") (pin "1") (pinfunction "1_1") (pintype "input"))
      (node (ref "C17") (pin "1") (pinfunction "1_1") (pintype "unspecified"))
      (node (ref "C2") (pin "2") (pinfunction "2_2") (pintype "input"))
      (node (ref "C3") (pin "2") (pinfunction "2_2") (pintype "input"))
      (node (ref "C34") (pin "1") (pinfunction "1_1") (pintype "input"))
      (node (ref "C35") (pin "1") (pinfunction "1_1") (pintype "unspecified"))
      (node (ref "C36") (pin "1") (pinfunction "1_1") (pintype "unspecified"))
      (node (ref "D1") (pin "2") (pinfunction "K_2") (pintype "input"))
      (node (ref "U3") (pin "1") (pinfunction "IN_1") (pintype "input"))
      (node (ref "U41") (pin "5") (pinfunction "V+_5") (pintype "input"))
      (node (ref "U41") (pin "7") (pinfunction "E/S_7") (pintype "input"))
      (node (ref "U8") (pin "2") (pinfunction "VIN_2") (pintype "input"))
    )
    (net (code "4") (name "DUT_VCC_RLY") (class "Default")
      (node (ref "H4") (pin "1") (pinfunction "1_1") (pintype "input"))
      (node (ref "H5") (pin "1") (pinfunction "1_1") (pintype "input"))
      (node (ref "K9") (pin "3") (pinfunction "3_3") (pintype "input"))
      (node (ref "U38") (pin "1") (pinfunction "1_1") (pintype "input"))
      (node (ref "U42") (pin "1") (pinfunction "1_1") (pintype "unspecified"))
      (node (ref "U42") (pin "2") (pinfunction "2_2") (pintype "unspecified"))
      (node (ref "U46") (pin "1") (pinfunction "1_1") (pintype "input"))
    )
    (net (code "5") (name "GND") (class "Default")
      (node (ref "C1") (pin "2") (pinfunction "2_2") (pintype "input"))
      (node (ref "C10") (pin "1") (pinfunction "1_1") (pintype "input"))
      (node (ref "C11") (pin "1") (pinfunction "1_1") (pintype "unspecified"))
      (node (ref "C12") (pin "2") (pinfunction "2_2") (pintype "input"))
      (node (ref "C13") (pin "2") (pinfunction "2_2") (pintype "unspecified"))
      (node (ref "C14") (pin "1") (pinfunction "1_1") (pintype "unspecified"))
      (node (ref "C15") (pin "1") (pinfunction "1_1") (pintype "input"))
      (node (ref "C16") (pin "2") (pinfunction "2_2") (pintype "input"))
      (node (ref "C17") (pin "2") (pinfunction "2_2") (pintype "unspecified"))
      (node (ref "C18") (pin "2") (pinfunction "2_2") (pintype "input"))
      (node (ref "C19") (pin "2") (pinfunction "2_2") (pintype "input"))
      (node (ref "C2") (pin "1") (pinfunction "1_1") (pintype "input"))
      (node (ref "C20") (pin "2") (pinfunction "2_2") (pintype "input"))
      (node (ref "C21") (pin "2") (pinfunction "2_2") (pintype "unspecified"))
      (node (ref "C22") (pin "1") (pinfunction "1_1") (pintype "input"))
      (node (ref "C23") (pin "1") (pinfunction "1_1") (pintype "unspecified"))
      (node (ref "C24") (pin "1") (pinfunction "1_1") (pintype "input"))
      (node (ref "C25") (pin "1") (pinfunction "1_1") (pintype "unspecified"))
      (node (ref "C26") (pin "2") (pinfunction "2_2") (pintype "input"))
      (node (ref "C27") (pin "2") (pinfunction "2_2") (pintype "input"))
      (node (ref "C28") (pin "2") (pinfunction "2_2") (pintype "input"))
      (node (ref "C29") (pin "2") (pinfunction "2_2") (pintype "input"))
      (node (ref "C3") (pin "1") (pinfunction "1_1") (pintype "input"))
      (node (ref "C30") (pin "2") (pinfunction "2_2") (pintype "input"))
      (node (ref "C31") (pin "2") (pinfunction "2_2") (pintype "input"))
      (node (ref "C32") (pin "2") (pinfunction "2_2") (pintype "unspecified"))
      (node (ref "C33") (pin "2") (pinfunction "2_2") (pintype "unspecified"))
      (node (ref "C34") (pin "2") (pinfunction "2_2") (pintype "input"))
      (node (ref "C35") (pin "2") (pinfunction "2_2") (pintype "unspecified"))
      (node (ref "C36") (pin "2") (pinfunction "2_2") (pintype "unspecified"))
      (node (ref "C37") (pin "1") (pinfunction "1_1") (pintype "unspecified"))
      (node (ref "C38") (pin "1") (pinfunction "1_1") (pintype "unspecified"))
      (node (ref "C39") (pin "1") (pinfunction "1_1") (pintype "input"))
      (node (ref "C4") (pin "1") (pinfunction "1_1") (pintype "input"))
      (node (ref "C40") (pin "1") (pinfunction "1_1") (pintype "input"))
      (node (ref "C41") (pin "1") (pinfunction "1_1") (pintype "input"))
      (node (ref "C42") (pin "1") (pinfunction "1_1") (pintype "input"))
      (node (ref "C43") (pin "1") (pinfunction "1_1") (pintype "unspecified"))
      (node (ref "C44") (pin "1") (pinfunction "1_1") (pintype "unspecified"))
      (node (ref "C45") (pin "1") (pinfunction "1_1") (pintype "unspecified"))
      (node (ref "C46") (pin "1") (pinfunction "1_1") (pintype "input"))
      (node (ref "C47") (pin "2") (pinfunction "2_2") (pintype "input"))
      (node (ref "C48") (pin "2") (pinfunction "2_2") (pintype "unspecified"))
      (node (ref "C5") (pin "1") (pinfunction "1_1") (pintype "input"))
      (node (ref "C6") (pin "1") (pinfunction "1_1") (pintype "input"))
      (node (ref "C7") (pin "2") (pinfunction "2_2") (pintype "unspecified"))
      (node (ref "C8") (pin "2") (pinfunction "2_2") (pintype "input"))
      (node (ref "C9") (pin "2") (pinfunction "2_2") (pintype "unspecified"))
      (node (ref "D2") (pin "2") (pinfunction "A_2") (pintype "unspecified"))
      (node (ref "D3") (pin "2") (pinfunction "A_2") (pintype "input"))
      (node (ref "H6") (pin "1") (pinfunction "1_1") (pintype "input"))
      (node (ref "H7") (pin "1") (pinfunction "1_1") (pintype "input"))
      (node (ref "J2") (pin "1") (pinfunction "1_1") (pintype "input"))
      (node (ref "J3") (pin "1") (pinfunction "1_1") (pintype "input"))
      (node (ref "J4") (pin "1") (pinfunction "1_1") (pintype "input"))
      (node (ref "J5") (pin "1") (pinfunction "1_1") (pintype "input"))
      (node (ref "LED13") (pin "1") (pinfunction "C_1") (pintype "input"))
      (node (ref "P2") (pin "2") (pinfunction "2_2") (pintype "unspecified"))
      (node (ref "Q1") (pin "2") (pinfunction "E_2") (pintype "input"))
      (node (ref "Q2") (pin "2") (pinfunction "E_2") (pintype "input"))
      (node (ref "Q3") (pin "2") (pinfunction "E_2") (pintype "input"))
      (node (ref "Q4") (pin "2") (pinfunction "E_2") (pintype "input"))
      (node (ref "Q5") (pin "2") (pinfunction "E_2") (pintype "input"))
      (node (ref "Q6") (pin "2") (pinfunction "E_2") (pintype "input"))
      (node (ref "Q7") (pin "2") (pinfunction "E_2") (pintype "input"))
      (node (ref "Q8") (pin "2") (pinfunction "E_2") (pintype "input"))
      (node (ref "Q9") (pin "2") (pinfunction "E_2") (pintype "input"))
      (node (ref "R14") (pin "1") (pinfunction "1_1") (pintype "input"))
      (node (ref "U1") (pin "23") (pinfunction "VSS_23") (pintype "input"))
      (node (ref "U1") (pin "47") (pinfunction "VSS_47") (pintype "input"))
      (node (ref "U1") (pin "8") (pinfunction "VSSA_8") (pintype "input"))
      (node (ref "U2") (pin "10") (pinfunction "10_10") (pintype "input"))
      (node (ref "U2") (pin "8") (pinfunction "8_8") (pintype "input"))
      (node (ref "U2") (pin "9") (pinfunction "9_9") (pintype "input"))
      (node (ref "U3") (pin "4") (pinfunction "GND_4") (pintype "input"))
      (node (ref "U4") (pin "1") (pinfunction "GND_1") (pintype "unspecified"))
      (node (ref "U41") (pin "3") (pinfunction "ILIM_3") (pintype "input"))
      (node (ref "U41") (pin "4") (pinfunction "V-_4") (pintype "input"))
      (node (ref "U41") (pin "8") (pinfunction "V-_8") (pintype "input"))
      (node (ref "U44") (pin "1") (pinfunction "1_1") (pintype "unspecified"))
      (node (ref "U44") (pin "2") (pinfunction "2_2") (pintype "unspecified"))
      (node (ref "U47") (pin "1") (pinfunction "1_1") (pintype "input"))
      (node (ref "U48") (pin "1") (pinfunction "1_1") (pintype "input"))
      (node (ref "U5") (pin "2") (pinfunction "AGND_2") (pintype "input"))
      (node (ref "U5") (pin "7") (pinfunction "DGND_7") (pintype "input"))
      (node (ref "U7") (pin "4") (pinfunction "V-_4") (pintype "unspecified"))
      (node (ref "U8") (pin "4") (pinfunction "GND_4") (pintype "input"))
      (node (ref "X1") (pin "2") (pinfunction "2_2") (pintype "input"))
      (node (ref "X1") (pin "4") (pinfunction "4_4") (pintype "input"))
    )
    (net (code "6") (name "LDO_5V") (class "Default")
      (node (ref "C12") (pin "1") (pinfunction "1_1") (pintype "input"))
      (node (ref "C13") (pin "1") (pinfunction "1_1") (pintype "unspecified"))
      (node (ref "C20") (pin "1") (pinfunction "1_1") (pintype "input"))
      (node (ref "C21") (pin "1") (pinfunction "1_1") (pintype "unspecified"))
      (node (ref "C22") (pin "2") (pinfunction "2_2") (pintype "input"))
      (node (ref "C23") (pin "2") (pinfunction "2_2") (pintype "unspecified"))
      (node (ref "C24") (pin "2") (pinfunction "2_2") (pintype "input"))
      (node (ref "C25") (pin "2") (pinfunction "2_2") (pintype "unspecified"))
      (node (ref "C45") (pin "2") (pinfunction "2_2") (pintype "unspecified"))
      (node (ref "C46") (pin "2") (pinfunction "2_2") (pintype "input"))
      (node (ref "C47") (pin "1") (pinfunction "1_1") (pintype "input"))
      (node (ref "C48") (pin "1") (pinfunction "1_1") (pintype "unspecified"))
      (node (ref "C7") (pin "1") (pinfunction "1_1") (pintype "unspecified"))
      (node (ref "C8") (pin "1") (pinfunction "1_1") (pintype "input"))
      (node (ref "D10") (pin "1") (pinfunction "K_1") (pintype "unspecified"))
      (node (ref "D11") (pin "1") (pinfunction "K_1") (pintype "unspecified"))
      (node (ref "D12") (pin "1") (pinfunction "K_1") (pintype "unspecified"))
      (node (ref "D13") (pin "1") (pinfunction "K_1") (pintype "input"))
      (node (ref "D14") (pin "1") (pinfunction "K_1") (pintype "input"))
      (node (ref "D15") (pin "1") (pinfunction "K_1") (pintype "input"))
      (node (ref "D4") (pin "1") (pinfunction "K_1") (pintype "unspecified"))
      (node (ref "D5") (pin "1") (pinfunction "K_1") (pintype "unspecified"))
      (node (ref "D6") (pin "1") (pinfunction "K_1") (pintype "unspecified"))
      (node (ref "D7") (pin "1") (pinfunction "K_1") (pintype "unspecified"))
      (node (ref "D8") (pin "1") (pinfunction "K_1") (pintype "unspecified"))
      (node (ref "D9") (pin "1") (pinfunction "K_1") (pintype "unspecified"))
      (node (ref "H1") (pin "2") (pinfunction "2_2") (pintype "input"))
      (node (ref "K1") (pin "1") (pinfunction "1_1") (pintype "input"))
      (node (ref "K2") (pin "1") (pinfunction "1_1") (pintype "input"))
      (node (ref "K3") (pin "1") (pinfunction "1_1") (pintype "input"))
      (node (ref "K4") (pin "1") (pinfunction "1_1") (pintype "input"))
      (node (ref "K5") (pin "1") (pinfunction "1_1") (pintype "input"))
      (node (ref "K6") (pin "1") (pinfunction "1_1") (pintype "input"))
      (node (ref "K7") (pin "1") (pinfunction "1_1") (pintype "input"))
      (node (ref "K8") (pin "1") (pinfunction "1_1") (pintype "input"))
      (node (ref "K9") (pin "1") (pinfunction "1_1") (pintype "input"))
      (node (ref "LED1") (pin "2") (pinfunction "A_2") (pintype "input"))
      (node (ref "LED2") (pin "2") (pinfunction "A_2") (pintype "input"))
      (node (ref "LED3") (pin "2") (pinfunction "A_2") (pintype "input"))
      (node (ref "R15") (pin "1") (pinfunction "1_1") (pintype "input"))
      (node (ref "R16") (pin "2") (pinfunction "2_2") (pintype "input"))
      (node (ref "U1") (pin "1") (pinfunction "VDD_1") (pintype "input"))
      (node (ref "U1") (pin "24") (pinfunction "VDD_24") (pintype "input"))
      (node (ref "U1") (pin "48") (pinfunction "VDD_48") (pintype "input"))
      (node (ref "U1") (pin "9") (pinfunction "VDDA_9") (pintype "input"))
      (node (ref "U4") (pin "16") (pinfunction "VCC_16") (pintype "unspecified"))
      (node (ref "U5") (pin "8") (pinfunction "VDD_8") (pintype "input"))
      (node (ref "U7") (pin "8") (pinfunction "V+_8") (pintype "unspecified"))
    )
    (net (code "7") (name "LED_BLUE") (class "Default")
      (node (ref "R2") (pin "1") (pinfunction "1_1") (pintype "input"))
      (node (ref "U1") (pin "3") (pinfunction "PC14_3") (pintype "input"))
    )
    (net (code "8") (name "LED_GREEN") (class "Default")
      (node (ref "R3") (pin "1") (pinfunction "1_1") (pintype "input"))
      (node (ref "U1") (pin "4") (pinfunction "PC15_4") (pintype "input"))
    )
    (net (code "9") (name "LED_RED") (class "Default")
      (node (ref "R1") (pin "1") (pinfunction "1_1") (pintype "input"))
      (node (ref "U1") (pin "2") (pinfunction "PC13_2") (pintype "input"))
    )
    (net (code "10") (name "MCO") (class "Default")
      (node (ref "U1") (pin "30") (pinfunction "PA9/CMP0_OUT/TIM1_CH2/UART1_TX/I2C1_SCL/MCO/TIM5_BKIN_30") (pintype "input"))
      (node (ref "U2") (pin "7") (pinfunction "7_7") (pintype "input"))
    )
    (net (code "11") (name "Net-(C26-Pad1)") (class "Default")
      (node (ref "C26") (pin "1") (pinfunction "1_1") (pintype "input"))
      (node (ref "K2") (pin "3") (pinfunction "3_3") (pintype "input"))
    )
    (net (code "12") (name "Net-(C27-Pad1)") (class "Default")
      (node (ref "C27") (pin "1") (pinfunction "1_1") (pintype "input"))
      (node (ref "K3") (pin "3") (pinfunction "3_3") (pintype "input"))
    )
    (net (code "13") (name "Net-(C28-Pad1)") (class "Default")
      (node (ref "C28") (pin "1") (pinfunction "1_1") (pintype "input"))
      (node (ref "C29") (pin "1") (pinfunction "1_1") (pintype "input"))
      (node (ref "K4") (pin "3") (pinfunction "3_3") (pintype "input"))
    )
    (net (code "14") (name "Net-(C30-Pad1)") (class "Default")
      (node (ref "C30") (pin "1") (pinfunction "1_1") (pintype "input"))
      (node (ref "C31") (pin "1") (pinfunction "1_1") (pintype "input"))
      (node (ref "K5") (pin "3") (pinfunction "3_3") (pintype "input"))
    )
    (net (code "15") (name "Net-(C32-Pad1)") (class "Default")
      (node (ref "C32") (pin "1") (pinfunction "1_1") (pintype "unspecified"))
      (node (ref "K6") (pin "3") (pinfunction "3_3") (pintype "input"))
    )
    (net (code "16") (name "Net-(C33-Pad1)") (class "Default")
      (node (ref "C33") (pin "1") (pinfunction "1_1") (pintype "unspecified"))
      (node (ref "K7") (pin "3") (pinfunction "3_3") (pintype "input"))
    )
    (net (code "17") (name "Net-(D1-A)") (class "Default")
      (node (ref "D1") (pin "1") (pinfunction "A_1") (pintype "input"))
      (node (ref "P2") (pin "1") (pinfunction "1_1") (pintype "unspecified"))
    )
    (net (code "18") (name "Net-(D3-K)") (class "Default")
      (node (ref "D3") (pin "1") (pinfunction "K_1") (pintype "input"))
      (node (ref "USB1") (pin "4") (pinfunction "GND_4") (pintype "input"))
      (node (ref "USB1") (pin "5") (pinfunction "GND_5") (pintype "input"))
      (node (ref "USB1") (pin "6") (pinfunction "GND_6") (pintype "input"))
    )
    (net (code "19") (name "Net-(D4-A)") (class "Default")
      (node (ref "D4") (pin "2") (pinfunction "A_2") (pintype "unspecified"))
      (node (ref "K1") (pin "2") (pinfunction "2_2") (pintype "input"))
      (node (ref "Q1") (pin "3") (pinfunction "C_3") (pintype "input"))
    )
    (net (code "20") (name "Net-(D5-A)") (class "Default")
      (node (ref "D5") (pin "2") (pinfunction "A_2") (pintype "unspecified"))
      (node (ref "K2") (pin "2") (pinfunction "2_2") (pintype "input"))
      (node (ref "Q2") (pin "3") (pinfunction "C_3") (pintype "input"))
    )
    (net (code "21") (name "Net-(D6-A)") (class "Default")
      (node (ref "D6") (pin "2") (pinfunction "A_2") (pintype "unspecified"))
      (node (ref "K3") (pin "2") (pinfunction "2_2") (pintype "input"))
      (node (ref "Q3") (pin "3") (pinfunction "C_3") (pintype "input"))
    )
    (net (code "22") (name "Net-(D7-A)") (class "Default")
      (node (ref "D7") (pin "2") (pinfunction "A_2") (pintype "unspecified"))
      (node (ref "K4") (pin "2") (pinfunction "2_2") (pintype "input"))
      (node (ref "Q4") (pin "3") (pinfunction "C_3") (pintype "input"))
    )
    (net (code "23") (name "Net-(D8-A)") (class "Default")
      (node (ref "D8") (pin "2") (pinfunction "A_2") (pintype "unspecified"))
      (node (ref "K5") (pin "2") (pinfunction "2_2") (pintype "input"))
      (node (ref "Q5") (pin "3") (pinfunction "C_3") (pintype "input"))
    )
    (net (code "24") (name "Net-(D9-A)") (class "Default")
      (node (ref "D9") (pin "2") (pinfunction "A_2") (pintype "unspecified"))
      (node (ref "K6") (pin "2") (pinfunction "2_2") (pintype "input"))
      (node (ref "Q6") (pin "3") (pinfunction "C_3") (pintype "input"))
    )
    (net (code "25") (name "Net-(D10-A)") (class "Default")
      (node (ref "D10") (pin "2") (pinfunction "A_2") (pintype "unspecified"))
      (node (ref "K7") (pin "2") (pinfunction "2_2") (pintype "input"))
      (node (ref "Q7") (pin "3") (pinfunction "C_3") (pintype "input"))
    )
    (net (code "26") (name "Net-(D11-A)") (class "Default")
      (node (ref "D11") (pin "2") (pinfunction "A_2") (pintype "unspecified"))
      (node (ref "K8") (pin "2") (pinfunction "2_2") (pintype "input"))
      (node (ref "Q8") (pin "3") (pinfunction "C_3") (pintype "input"))
    )
    (net (code "27") (name "Net-(D12-A)") (class "Default")
      (node (ref "D12") (pin "2") (pinfunction "A_2") (pintype "unspecified"))
      (node (ref "K9") (pin "2") (pinfunction "2_2") (pintype "input"))
      (node (ref "Q9") (pin "3") (pinfunction "C_3") (pintype "input"))
    )
    (net (code "28") (name "Net-(D13-A)") (class "Default")
      (node (ref "D13") (pin "2") (pinfunction "A_2") (pintype "input"))
      (node (ref "D2") (pin "1") (pinfunction "K_1") (pintype "unspecified"))
      (node (ref "USB1") (pin "1") (pinfunction "VBUS_1") (pintype "input"))
    )
    (net (code "29") (name "Net-(D14-A)") (class "Default")
      (node (ref "D14") (pin "2") (pinfunction "A_2") (pintype "input"))
      (node (ref "U2") (pin "1") (pinfunction "1_1") (pintype "input"))
    )
    (net (code "30") (name "Net-(D15-A)") (class "Default")
      (node (ref "C4") (pin "2") (pinfunction "2_2") (pintype "input"))
      (node (ref "D15") (pin "2") (pinfunction "A_2") (pintype "input"))
      (node (ref "U3") (pin "3") (pinfunction "OUT_3") (pintype "input"))
    )
    (net (code "31") (name "Net-(H1-Pad1)") (class "Default")
      (node (ref "H1") (pin "1") (pinfunction "1_1") (pintype "input"))
      (node (ref "K1") (pin "3") (pinfunction "3_3") (pintype "input"))
      (node (ref "R15") (pin "2") (pinfunction "2_2") (pintype "input"))
    )
    (net (code "32") (name "Net-(K1-Pad4)") (class "Default")
      (node (ref "K1") (pin "4") (pinfunction "4_4") (pintype "input"))
      (node (ref "K2") (pin "4") (pinfunction "4_4") (pintype "input"))
      (node (ref "K3") (pin "4") (pinfunction "4_4") (pintype "input"))
      (node (ref "K4") (pin "4") (pinfunction "4_4") (pintype "input"))
      (node (ref "K5") (pin "4") (pinfunction "4_4") (pintype "input"))
      (node (ref "K6") (pin "4") (pinfunction "4_4") (pintype "input"))
      (node (ref "K7") (pin "4") (pinfunction "4_4") (pintype "input"))
      (node (ref "K8") (pin "3") (pinfunction "3_3") (pintype "input"))
      (node (ref "K9") (pin "4") (pinfunction "4_4") (pintype "input"))
    )
    (net (code "33") (name "Net-(K8-Pad4)") (class "Default")
      (node (ref "K8") (pin "4") (pinfunction "4_4") (pintype "input"))
      (node (ref "R14") (pin "2") (pinfunction "2_2") (pintype "input"))
    )
    (net (code "34") (name "Net-(L1-Pad1)") (class "Default")
      (node (ref "L1") (pin "1") (pinfunction "1_1") (pintype "unspecified"))
      (node (ref "R17") (pin "2") (pinfunction "2_2") (pintype "unspecified"))
    )
    (net (code "35") (name "Net-(LED1-K)") (class "Default")
      (node (ref "LED1") (pin "1") (pinfunction "K_1") (pintype "input"))
      (node (ref "R1") (pin "2") (pinfunction "2_2") (pintype "input"))
    )
    (net (code "36") (name "Net-(LED2-C)") (class "Default")
      (node (ref "LED2") (pin "1") (pinfunction "C_1") (pintype "input"))
      (node (ref "R2") (pin "2") (pinfunction "2_2") (pintype "input"))
    )
    (net (code "37") (name "Net-(LED3-C)") (class "Default")
      (node (ref "LED3") (pin "1") (pinfunction "C_1") (pintype "input"))
      (node (ref "R3") (pin "2") (pinfunction "2_2") (pintype "input"))
    )
    (net (code "38") (name "Net-(LED4-A)") (class "Default")
      (node (ref "LED4") (pin "2") (pinfunction "A_2") (pintype "input"))
      (node (ref "R5") (pin "2") (pinfunction "2_2") (pintype "input"))
    )
    (net (code "39") (name "Net-(LED4-C)") (class "Default")
      (node (ref "LED4") (pin "1") (pinfunction "C_1") (pintype "input"))
      (node (ref "Q1") (pin "1") (pinfunction "B_1") (pintype "input"))
    )
    (net (code "40") (name "Net-(LED5-A)") (class "Default")
      (node (ref "LED5") (pin "2") (pinfunction "A_2") (pintype "input"))
      (node (ref "R6") (pin "2") (pinfunction "2_2") (pintype "input"))
    )
    (net (code "41") (name "Net-(LED5-C)") (class "Default")
      (node (ref "LED5") (pin "1") (pinfunction "C_1") (pintype "input"))
      (node (ref "Q2") (pin "1") (pinfunction "B_1") (pintype "input"))
    )
    (net (code "42") (name "Net-(LED6-A)") (class "Default")
      (node (ref "LED6") (pin "2") (pinfunction "A_2") (pintype "input"))
      (node (ref "R7") (pin "2") (pinfunction "2_2") (pintype "input"))
    )
    (net (code "43") (name "Net-(LED6-C)") (class "Default")
      (node (ref "LED6") (pin "1") (pinfunction "C_1") (pintype "input"))
      (node (ref "Q3") (pin "1") (pinfunction "B_1") (pintype "input"))
    )
    (net (code "44") (name "Net-(LED7-A)") (class "Default")
      (node (ref "LED7") (pin "2") (pinfunction "A_2") (pintype "input"))
      (node (ref "R8") (pin "2") (pinfunction "2_2") (pintype "input"))
    )
    (net (code "45") (name "Net-(LED7-C)") (class "Default")
      (node (ref "LED7") (pin "1") (pinfunction "C_1") (pintype "input"))
      (node (ref "Q4") (pin "1") (pinfunction "B_1") (pintype "input"))
    )
    (net (code "46") (name "Net-(LED8-A)") (class "Default")
      (node (ref "LED8") (pin "2") (pinfunction "A_2") (pintype "input"))
      (node (ref "R9") (pin "2") (pinfunction "2_2") (pintype "input"))
    )
    (net (code "47") (name "Net-(LED8-C)") (class "Default")
      (node (ref "LED8") (pin "1") (pinfunction "C_1") (pintype "input"))
      (node (ref "Q5") (pin "1") (pinfunction "B_1") (pintype "input"))
    )
    (net (code "48") (name "Net-(LED9-A)") (class "Default")
      (node (ref "LED9") (pin "2") (pinfunction "A_2") (pintype "input"))
      (node (ref "R10") (pin "2") (pinfunction "2_2") (pintype "input"))
    )
    (net (code "49") (name "Net-(LED9-C)") (class "Default")
      (node (ref "LED9") (pin "1") (pinfunction "C_1") (pintype "input"))
      (node (ref "Q6") (pin "1") (pinfunction "B_1") (pintype "input"))
    )
    (net (code "50") (name "Net-(LED10-A)") (class "Default")
      (node (ref "LED10") (pin "2") (pinfunction "A_2") (pintype "input"))
      (node (ref "R11") (pin "2") (pinfunction "2_2") (pintype "input"))
    )
    (net (code "51") (name "Net-(LED10-C)") (class "Default")
      (node (ref "LED10") (pin "1") (pinfunction "C_1") (pintype "input"))
      (node (ref "Q7") (pin "1") (pinfunction "B_1") (pintype "input"))
    )
    (net (code "52") (name "Net-(LED11-A)") (class "Default")
      (node (ref "LED11") (pin "2") (pinfunction "A_2") (pintype "input"))
      (node (ref "R12") (pin "2") (pinfunction "2_2") (pintype "input"))
    )
    (net (code "53") (name "Net-(LED11-C)") (class "Default")
      (node (ref "LED11") (pin "1") (pinfunction "C_1") (pintype "input"))
      (node (ref "Q8") (pin "1") (pinfunction "B_1") (pintype "input"))
    )
    (net (code "54") (name "Net-(LED12-A)") (class "Default")
      (node (ref "LED12") (pin "2") (pinfunction "A_2") (pintype "input"))
      (node (ref "R13") (pin "2") (pinfunction "2_2") (pintype "input"))
    )
    (net (code "55") (name "Net-(LED12-C)") (class "Default")
      (node (ref "LED12") (pin "1") (pinfunction "C_1") (pintype "input"))
      (node (ref "Q9") (pin "1") (pinfunction "B_1") (pintype "input"))
    )
    (net (code "56") (name "Net-(LED13-A)") (class "Default")
      (node (ref "LED13") (pin "2") (pinfunction "A_2") (pintype "input"))
      (node (ref "R16") (pin "1") (pinfunction "1_1") (pintype "input"))
    )
    (net (code "57") (name "Net-(U4-V3)") (class "Default")
      (node (ref "C9") (pin "1") (pinfunction "1_1") (pintype "unspecified"))
      (node (ref "U4") (pin "4") (pinfunction "V3_4") (pintype "unspecified"))
    )
    (net (code "58") (name "Net-(U4-XI)") (class "Default")
      (node (ref "C5") (pin "2") (pinfunction "2_2") (pintype "input"))
      (node (ref "U4") (pin "7") (pinfunction "XI_7") (pintype "unspecified"))
      (node (ref "X2") (pin "1") (pinfunction "OSC1_1") (pintype "input"))
    )
    (net (code "59") (name "Net-(U4-XO)") (class "Default")
      (node (ref "C6") (pin "2") (pinfunction "2_2") (pintype "input"))
      (node (ref "U4") (pin "8") (pinfunction "XO_8") (pintype "unspecified"))
      (node (ref "X2") (pin "2") (pinfunction "OSC2_2") (pintype "input"))
    )
    (net (code "60") (name "Net-(U7A-IN_B-)") (class "Default")
      (node (ref "R4") (pin "1") (pinfunction "1_1") (pintype "input"))
      (node (ref "U7") (pin "6") (pinfunction "IN_B-_6") (pintype "unspecified"))
      (node (ref "U7") (pin "7") (pinfunction "OUT_B_7") (pintype "output"))
    )
    (net (code "61") (name "Net-(U8A-TRIMNR)") (class "Default")
      (node (ref "C15") (pin "2") (pinfunction "2_2") (pintype "input"))
      (node (ref "U8") (pin "5") (pinfunction "TRIMNR_5") (pintype "input"))
    )
    (net (code "62") (name "Net-(U41-VIN-)") (class "Default")
      (node (ref "R17") (pin "1") (pinfunction "1_1") (pintype "unspecified"))
      (node (ref "U41") (pin "2") (pinfunction "VIN-_2") (pintype "input"))
      (node (ref "U41") (pin "6") (pinfunction "VO_6") (pintype "input"))
    )
    (net (code "63") (name "OPA1_OUT_VCC") (class "Default")
      (node (ref "C14") (pin "2") (pinfunction "2_2") (pintype "unspecified"))
      (node (ref "R4") (pin "2") (pinfunction "2_2") (pintype "input"))
      (node (ref "U41") (pin "1") (pinfunction "VIN+_1") (pintype "input"))
    )
    (net (code "64") (name "OSC_IN") (class "Default")
      (node (ref "U1") (pin "5") (pinfunction "PF0/OSC_IN/I2C0_SDA_5") (pintype "input"))
      (node (ref "X1") (pin "1") (pinfunction "OSC1_1") (pintype "input"))
    )
    (net (code "65") (name "OSC_OUT") (class "Default")
      (node (ref "U1") (pin "6") (pinfunction "PF1/OSC_OUT/I2C0_SCL_6") (pintype "input"))
      (node (ref "X1") (pin "3") (pinfunction "OSC2_3") (pintype "input"))
    )
    (net (code "66") (name "REF_5V") (class "Default")
      (node (ref "C10") (pin "2") (pinfunction "2_2") (pintype "input"))
      (node (ref "C11") (pin "2") (pinfunction "2_2") (pintype "unspecified"))
      (node (ref "C18") (pin "1") (pinfunction "1_1") (pintype "input"))
      (node (ref "C19") (pin "1") (pinfunction "1_1") (pintype "input"))
      (node (ref "U5") (pin "3") (pinfunction "REF_3") (pintype "input"))
      (node (ref "U8") (pin "6") (pinfunction "VOUT_6") (pintype "output"))
    )
    (net (code "67") (name "RLY1_CTRL") (class "Default")
      (node (ref "R5") (pin "1") (pinfunction "1_1") (pintype "input"))
      (node (ref "U1") (pin "38") (pinfunction "PA15/SPI1_CS/UART1_RX/UART0_RX/CMP0_P0_38") (pintype "input"))
    )
    (net (code "68") (name "RLY2_CTRL") (class "Default")
      (node (ref "R6") (pin "1") (pinfunction "1_1") (pintype "input"))
      (node (ref "U1") (pin "39") (pinfunction "PB3/SPI1_SCK/ADC_IN10/CMP0_N_39") (pintype "input"))
    )
    (net (code "69") (name "RLY3_CTRL") (class "Default")
      (node (ref "R7") (pin "1") (pinfunction "1_1") (pintype "input"))
      (node (ref "U1") (pin "40") (pinfunction "PB4/SPI1_MISO/CMP0_OUT/TIM7_BKIN/ADC_IN11_40") (pintype "input"))
    )
    (net (code "70") (name "RLY4_CTRL") (class "Default")
      (node (ref "R8") (pin "1") (pinfunction "1_1") (pintype "input"))
      (node (ref "U1") (pin "41") (pinfunction "PB5/SPI1_MOSI/TIM6_BKIN/ADC_IN13/CMP2_N_41") (pintype "input"))
    )
    (net (code "71") (name "RLY5_CTRL") (class "Default")
      (node (ref "R9") (pin "1") (pinfunction "1_1") (pintype "input"))
      (node (ref "U1") (pin "42") (pinfunction "PB6/I2C1_SCL/UART1_TX/UART0_TX/I2C0_SCL/TIM6_CH1N/ADC_IN14/CMP2_N_42") (pintype "input"))
    )
    (net (code "72") (name "RLY6_CTRL") (class "Default")
      (node (ref "R10") (pin "1") (pinfunction "1_1") (pintype "input"))
      (node (ref "U1") (pin "43") (pinfunction "PB7/I2C1_SDA/UART1_RX/UART0_RX/I2C0_SDA/CMP2_OUT/TIM7/CJ1N/ADC_IN15_43") (pintype "input"))
    )
    (net (code "73") (name "RLY7_CTRL") (class "Default")
      (node (ref "R11") (pin "1") (pinfunction "1_1") (pintype "input"))
      (node (ref "U1") (pin "44") (pinfunction "PB2/BEEP1/MCO/CMP1_OUT/ADC_IN9_44") (pintype "input"))
    )
    (net (code "74") (name "RLY8_CTRL") (class "Default")
      (node (ref "R12") (pin "1") (pinfunction "1_1") (pintype "input"))
      (node (ref "U1") (pin "45") (pinfunction "PB8/I2C0_SCL/TIM6_CH1/CMP2_P1_45") (pintype "input"))
    )
    (net (code "75") (name "RLY9_CTRL") (class "Default")
      (node (ref "R13") (pin "1") (pinfunction "1_1") (pintype "input"))
      (node (ref "U1") (pin "46") (pinfunction "PB9/IR_TXD/I2C0_SDA/TIM7_CH1/CMP2_P2_46") (pintype "input"))
    )
    (net (code "76") (name "RSTN") (class "Default")
      (node (ref "U1") (pin "7") (pinfunction "NRST_7") (pintype "input"))
      (node (ref "U2") (pin "6") (pinfunction "6_6") (pintype "input"))
    )
    (net (code "77") (name "SPI_CS") (class "Default")
      (node (ref "U1") (pin "25") (pinfunction "PB12/SPI0_CS/TIM1_BKIN/SPI1_CS_25") (pintype "input"))
      (node (ref "U5") (pin "4") (pinfunction "CS#_4") (pintype "input"))
    )
    (net (code "78") (name "SPI_MOSI") (class "Default")
      (node (ref "U1") (pin "28") (pinfunction "PB15/SPI0_MOSI/TIM1_CH3N/SPI1_MOSI/TIM5_CH1N_28") (pintype "input"))
      (node (ref "U5") (pin "6") (pinfunction "DIN_6") (pintype "input"))
    )
    (net (code "79") (name "SPI_SCK") (class "Default")
      (node (ref "U1") (pin "26") (pinfunction "PB13/SPI0_SCK/TIM1_CH1N/SPI1_SCK/I2C1_SDA_26") (pintype "input"))
      (node (ref "U5") (pin "5") (pinfunction "SCLK_5") (pintype "input"))
    )
    (net (code "80") (name "SWCLK") (class "Default")
      (node (ref "U1") (pin "37") (pinfunction "PA14/SWCLK/UART1_TX/UART0_TX_37") (pintype "input"))
      (node (ref "U2") (pin "3") (pinfunction "3_3") (pintype "input"))
    )
    (net (code "81") (name "SWDIO") (class "Default")
      (node (ref "U1") (pin "34") (pinfunction "PA13/SWDIO/IR_TXD_34") (pintype "input"))
      (node (ref "U2") (pin "2") (pinfunction "2_2") (pintype "input"))
    )
    (net (code "82") (name "UART_RX") (class "Default")
      (node (ref "U1") (pin "13") (pinfunction "PA3/UART0_RX/UART1_RX/ADC_IN3/OPA0_P_13") (pintype "input"))
      (node (ref "U2") (pin "5") (pinfunction "5_5") (pintype "input"))
      (node (ref "U4") (pin "2") (pinfunction "TXD_2") (pintype "unspecified"))
    )
    (net (code "83") (name "UART_TX") (class "Default")
      (node (ref "U1") (pin "12") (pinfunction "PA2/UART0_TX/UART1_TX/TIM5_CH1/ADC_IN2/CMP2_P3/OPA1_OUT_12") (pintype "input"))
      (node (ref "U2") (pin "4") (pinfunction "4_4") (pintype "input"))
      (node (ref "U4") (pin "3") (pinfunction "RXD_3") (pintype "unspecified"))
    )
    (net (code "84") (name "USB_D+") (class "Default")
      (node (ref "U4") (pin "5") (pinfunction "UD+_5") (pintype "unspecified"))
      (node (ref "USB1") (pin "3") (pinfunction "D+_3") (pintype "input"))
    )
    (net (code "85") (name "USB_D-") (class "Default")
      (node (ref "U4") (pin "6") (pinfunction "UD-_6") (pintype "unspecified"))
      (node (ref "USB1") (pin "2") (pinfunction "D-_2") (pintype "input"))
    )
    (net (code "86") (name "unconnected-(U1-PA0{slash}ADC_IN0{slash}VREF+{slash}CMP1_P{slash}OPA1_P-Pad10)") (class "Default")
      (node (ref "U1") (pin "10") (pinfunction "PA0/ADC_IN0/VREF+/CMP1_P/OPA1_P_10") (pintype "input+no_connect"))
    )
    (net (code "87") (name "unconnected-(U1-PA1{slash}ADC_IN1{slash}CMP1_N{slash}OPA1_N-Pad11)") (class "Default")
      (node (ref "U1") (pin "11") (pinfunction "PA1/ADC_IN1/CMP1_N/OPA1_N_11") (pintype "input+no_connect"))
    )
    (net (code "88") (name "unconnected-(U1-PA4{slash}SPI0_CS{slash}UART1_TX{slash}UART0_TX-Pad14)") (class "Default")
      (node (ref "U1") (pin "14") (pinfunction "PA4/SPI0_CS/UART1_TX/UART0_TX_14") (pintype "input+no_connect"))
    )
    (net (code "89") (name "unconnected-(U1-PA5{slash}SPI0_SCK{slash}UART1_RX{slash}UART0_RX{slash}ADC_IN5{slash}CMP0_P3{slash}OPA0_OUT-Pad15)") (class "Default")
      (node (ref "U1") (pin "15") (pinfunction "PA5/SPI0_SCK/UART1_RX/UART0_RX/ADC_IN5/CMP0_P3/OPA0_OUT_15") (pintype "input+no_connect"))
    )
    (net (code "90") (name "unconnected-(U1-PA6{slash}SPI0_MISO{slash}TIM1_BKIN{slash}TIM6{slash}CH1{slash}ADC_IN6-Pad16)") (class "Default")
      (node (ref "U1") (pin "16") (pinfunction "PA6/SPI0_MISO/TIM1_BKIN/TIM6/CH1/ADC_IN6_16") (pintype "input+no_connect"))
    )
    (net (code "91") (name "unconnected-(U1-PA7{slash}SPI0_MOSI{slash}TIM1_CJ1N{slash}ADC_ETR{slash}TIM7_CH1{slash}ADC_IN7-Pad17)") (class "Default")
      (node (ref "U1") (pin "17") (pinfunction "PA7/SPI0_MOSI/TIM1_CJ1N/ADC_ETR/TIM7_CH1/ADC_IN7_17") (pintype "input+no_connect"))
    )
    (net (code "92") (name "unconnected-(U1-PA8{slash}MCO{slash}TIM1_CH1{slash}CMP2_OUT-Pad29)") (class "Default")
      (node (ref "U1") (pin "29") (pinfunction "PA8/MCO/TIM1_CH1/CMP2_OUT_29") (pintype "input+no_connect"))
    )
    (net (code "93") (name "unconnected-(U1-PA10{slash}CMP1_OUT{slash}TIM1_CH3{slash}UART1_RX{slash}I2C1_SDA{slash}TIM7_BKIN-Pad31)") (class "Default")
      (node (ref "U1") (pin "31") (pinfunction "PA10/CMP1_OUT/TIM1_CH3/UART1_RX/I2C1_SDA/TIM7_BKIN_31") (pintype "input+no_connect"))
    )
    (net (code "94") (name "unconnected-(U1-PA11{slash}I2C1_SCL{slash}TIM1_CH4{slash}I2C0_SCL-Pad32)") (class "Default")
      (node (ref "U1") (pin "32") (pinfunction "PA11/I2C1_SCL/TIM1_CH4/I2C0_SCL_32") (pintype "input+no_connect"))
    )
    (net (code "95") (name "unconnected-(U1-PA12{slash}I2C1_SDA{slash}TIM1_CH4N{slash}I2C0_SDA{slash}TIM1_ETR-Pad33)") (class "Default")
      (node (ref "U1") (pin "33") (pinfunction "PA12/I2C1_SDA/TIM1_CH4N/I2C0_SDA/TIM1_ETR_33") (pintype "input+no_connect"))
    )
    (net (code "96") (name "unconnected-(U1-PB0{slash}TIM1_CH2N{slash}ADC_IN12-Pad18)") (class "Default")
      (node (ref "U1") (pin "18") (pinfunction "PB0/TIM1_CH2N/ADC_IN12_18") (pintype "input+no_connect"))
    )
    (net (code "97") (name "unconnected-(U1-PB1{slash}IR_TXD{slash}TIM1_3N{slash}ADC_IN8-Pad19)") (class "Default")
      (node (ref "U1") (pin "19") (pinfunction "PB1/IR_TXD/TIM1_3N/ADC_IN8_19") (pintype "input+no_connect"))
    )
    (net (code "98") (name "unconnected-(U1-PB10{slash}SPI1_SCK{slash}I2C0_SCL{slash}I2C1_SCL{slash}TIM6_CH1{slash}CMP_P1-Pad21)") (class "Default")
      (node (ref "U1") (pin "21") (pinfunction "PB10/SPI1_SCK/I2C0_SCL/I2C1_SCL/TIM6_CH1/CMP_P1_21") (pintype "input+no_connect"))
    )
    (net (code "99") (name "unconnected-(U1-PB11{slash}I2C0_SDA{slash}I2C1_SDA{slash}TIM7_CH1{slash}CMP0_P2-Pad22)") (class "Default")
      (node (ref "U1") (pin "22") (pinfunction "PB11/I2C0_SDA/I2C1_SDA/TIM7_CH1/CMP0_P2_22") (pintype "input+no_connect"))
    )
    (net (code "100") (name "unconnected-(U1-PB14{slash}SPI0_MISO{slash}TIM1_CH2N{slash}SPI1_MISO{slash}TIM5_CH1-Pad27)") (class "Default")
      (node (ref "U1") (pin "27") (pinfunction "PB14/SPI0_MISO/TIM1_CH2N/SPI1_MISO/TIM5_CH1_27") (pintype "input+no_connect"))
    )
    (net (code "101") (name "unconnected-(U1-PF2{slash}TIM5_CH1-Pad20)") (class "Default")
      (node (ref "U1") (pin "20") (pinfunction "PF2/TIM5_CH1_20") (pintype "input+no_connect"))
    )
    (net (code "102") (name "unconnected-(U1-PF6{slash}I2C1_SCL{slash}I2C0_SCL-Pad35)") (class "Default")
      (node (ref "U1") (pin "35") (pinfunction "PF6/I2C1_SCL/I2C0_SCL_35") (pintype "input+no_connect"))
    )
    (net (code "103") (name "unconnected-(U1-PF7{slash}I2C1_SDA{slash}I2C0_SDA-Pad36)") (class "Default")
      (node (ref "U1") (pin "36") (pinfunction "PF7/I2C1_SDA/I2C0_SDA_36") (pintype "input+no_connect"))
    )
    (net (code "104") (name "unconnected-(U4-CTS#-Pad9)") (class "Default")
      (node (ref "U4") (pin "9") (pinfunction "CTS#_9") (pintype "unspecified+no_connect"))
    )
    (net (code "105") (name "unconnected-(U4-DCD#-Pad12)") (class "Default")
      (node (ref "U4") (pin "12") (pinfunction "DCD#_12") (pintype "unspecified+no_connect"))
    )
    (net (code "106") (name "unconnected-(U4-DSR#-Pad10)") (class "Default")
      (node (ref "U4") (pin "10") (pinfunction "DSR#_10") (pintype "unspecified+no_connect"))
    )
    (net (code "107") (name "unconnected-(U4-DTR#-Pad13)") (class "Default")
      (node (ref "U4") (pin "13") (pinfunction "DTR#_13") (pintype "unspecified+no_connect"))
    )
    (net (code "108") (name "unconnected-(U4-R232-Pad15)") (class "Default")
      (node (ref "U4") (pin "15") (pinfunction "R232_15") (pintype "unspecified+no_connect"))
    )
    (net (code "109") (name "unconnected-(U4-RI#-Pad11)") (class "Default")
      (node (ref "U4") (pin "11") (pinfunction "RI#_11") (pintype "unspecified+no_connect"))
    )
    (net (code "110") (name "unconnected-(U4-RTS#-Pad14)") (class "Default")
      (node (ref "U4") (pin "14") (pinfunction "RTS#_14") (pintype "unspecified+no_connect"))
    )
    (net (code "111") (name "unconnected-(U7B-IN_A+-Pad3)") (class "Default")
      (node (ref "U7") (pin "3") (pinfunction "IN_A+_3") (pintype "unspecified+no_connect"))
    )
    (net (code "112") (name "unconnected-(U7B-IN_A--Pad2)") (class "Default")
      (node (ref "U7") (pin "2") (pinfunction "IN_A-_2") (pintype "unspecified+no_connect"))
    )
    (net (code "113") (name "unconnected-(U7B-OUT_A-Pad1)") (class "Default")
      (node (ref "U7") (pin "1") (pinfunction "OUT_A_1") (pintype "output+no_connect"))
    )
    (net (code "114") (name "unconnected-(U8A-TEMP-Pad3)") (class "Default")
      (node (ref "U8") (pin "3") (pinfunction "TEMP_3") (pintype "output+no_connect"))
    )
    (net (code "115") (name "unconnected-(U8B-DNC-Pad1)") (class "Default")
      (node (ref "U8") (pin "1") (pinfunction "DNC_1") (pintype "input+no_connect"))
    )
    (net (code "116") (name "unconnected-(U8B-DNC-Pad8)") (class "Default")
      (node (ref "U8") (pin "8") (pinfunction "DNC_8") (pintype "input+no_connect"))
    )
    (net (code "117") (name "unconnected-(U8B-NC-Pad7)") (class "Default")
      (node (ref "U8") (pin "7") (pinfunction "NC_7") (pintype "input+no_connect"))
    )
  )
)
